# zx_kit3.net
KiCad netlist of a schematic drawn in EAGLE
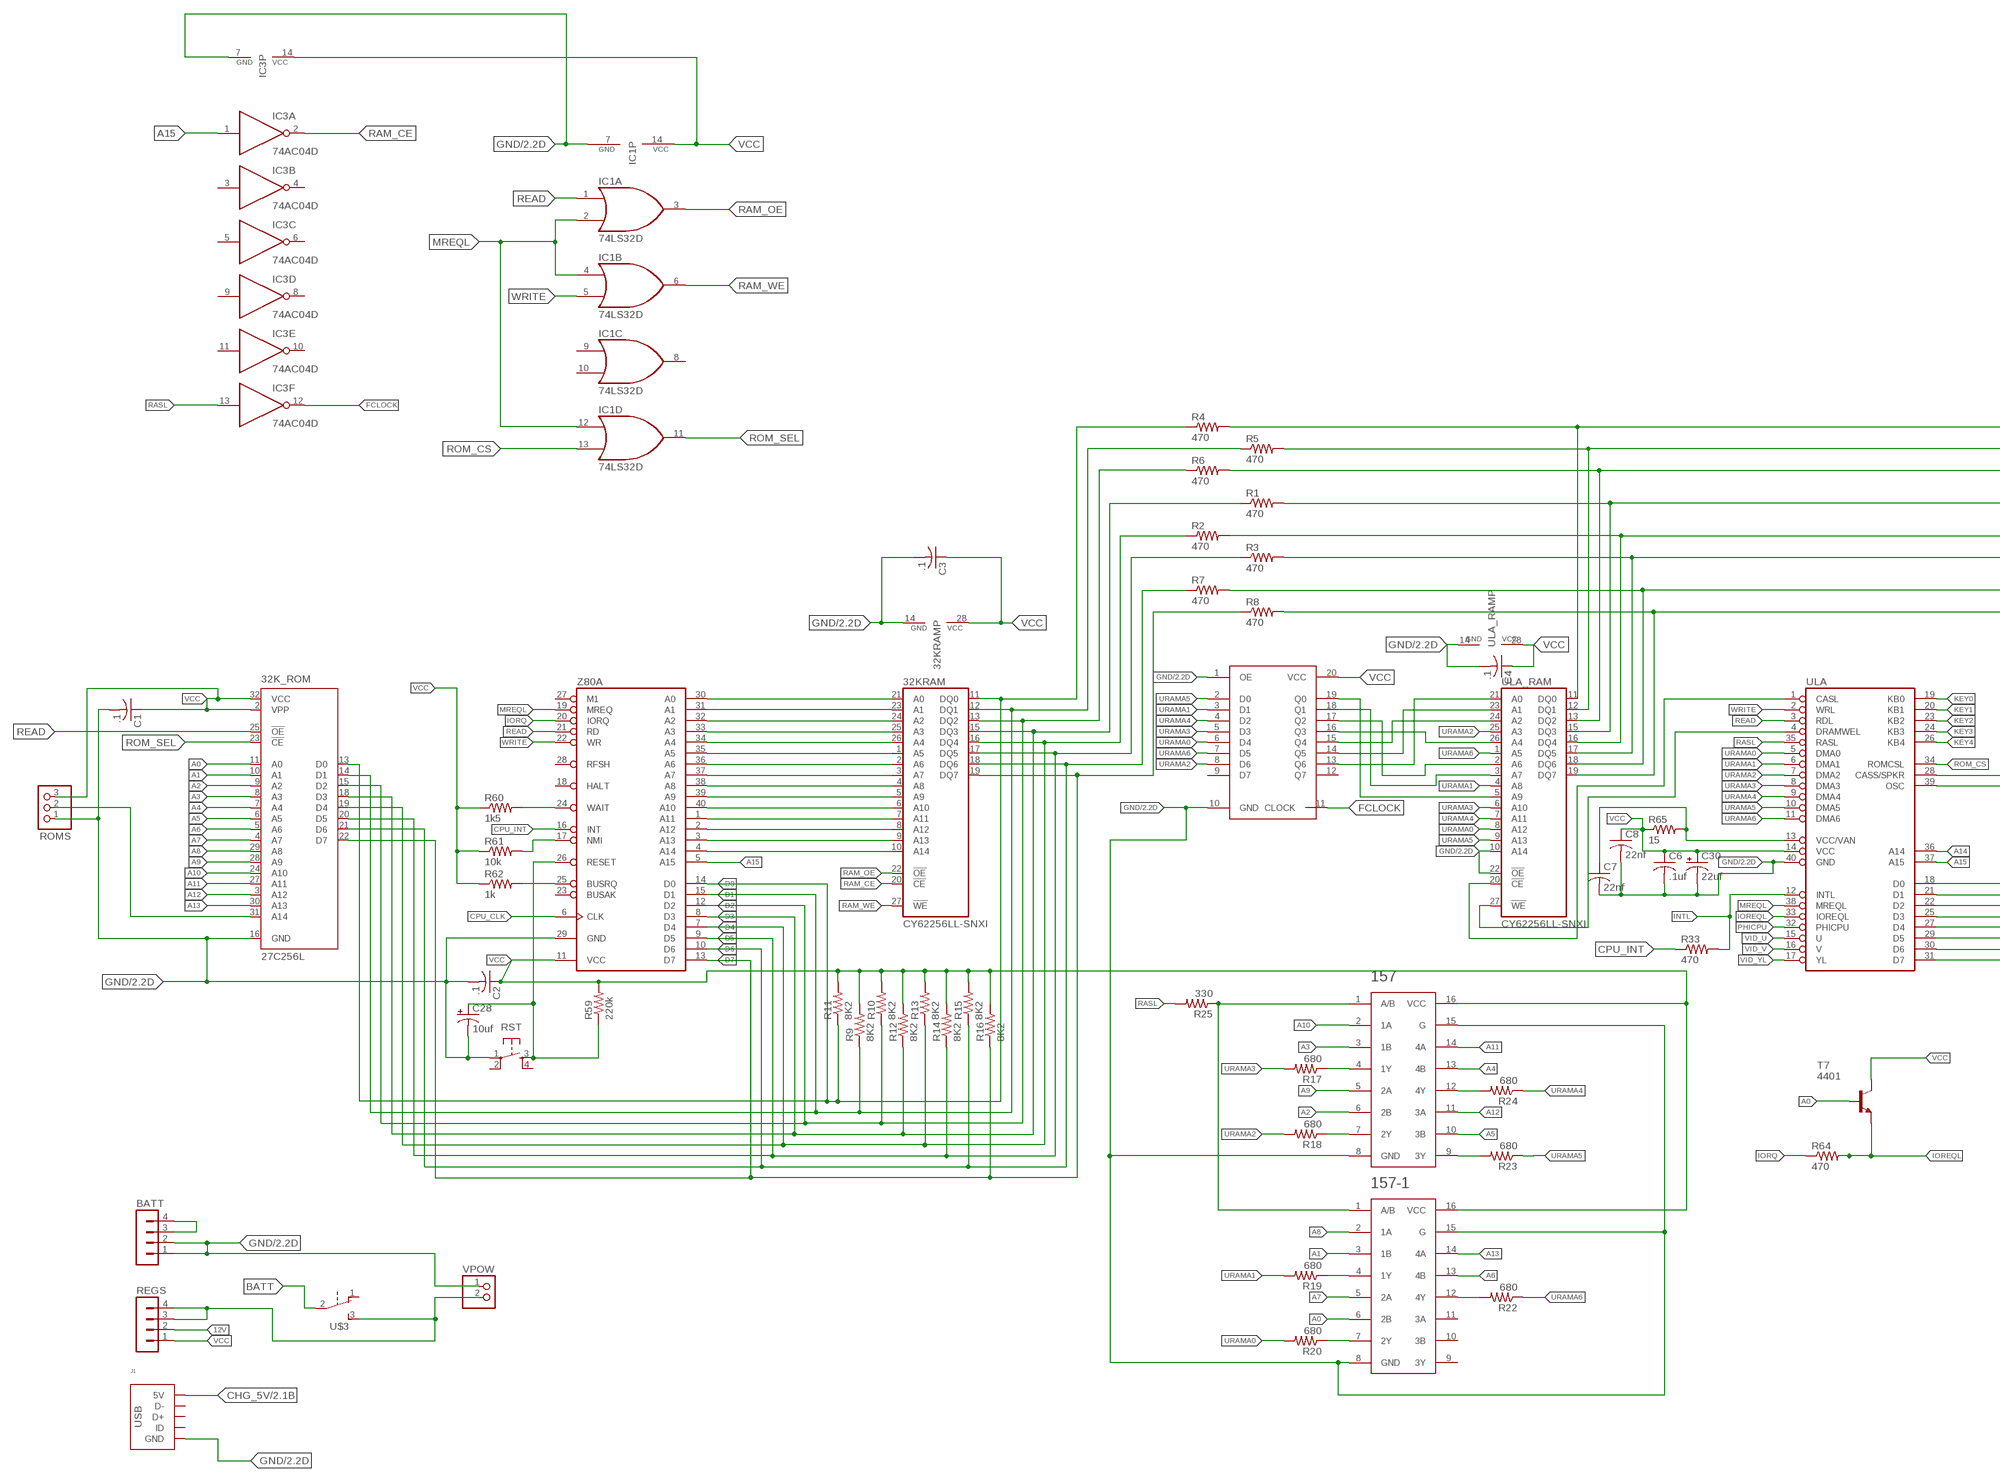
[diagram p0: schematic, sheet 1, part 1 of 3]
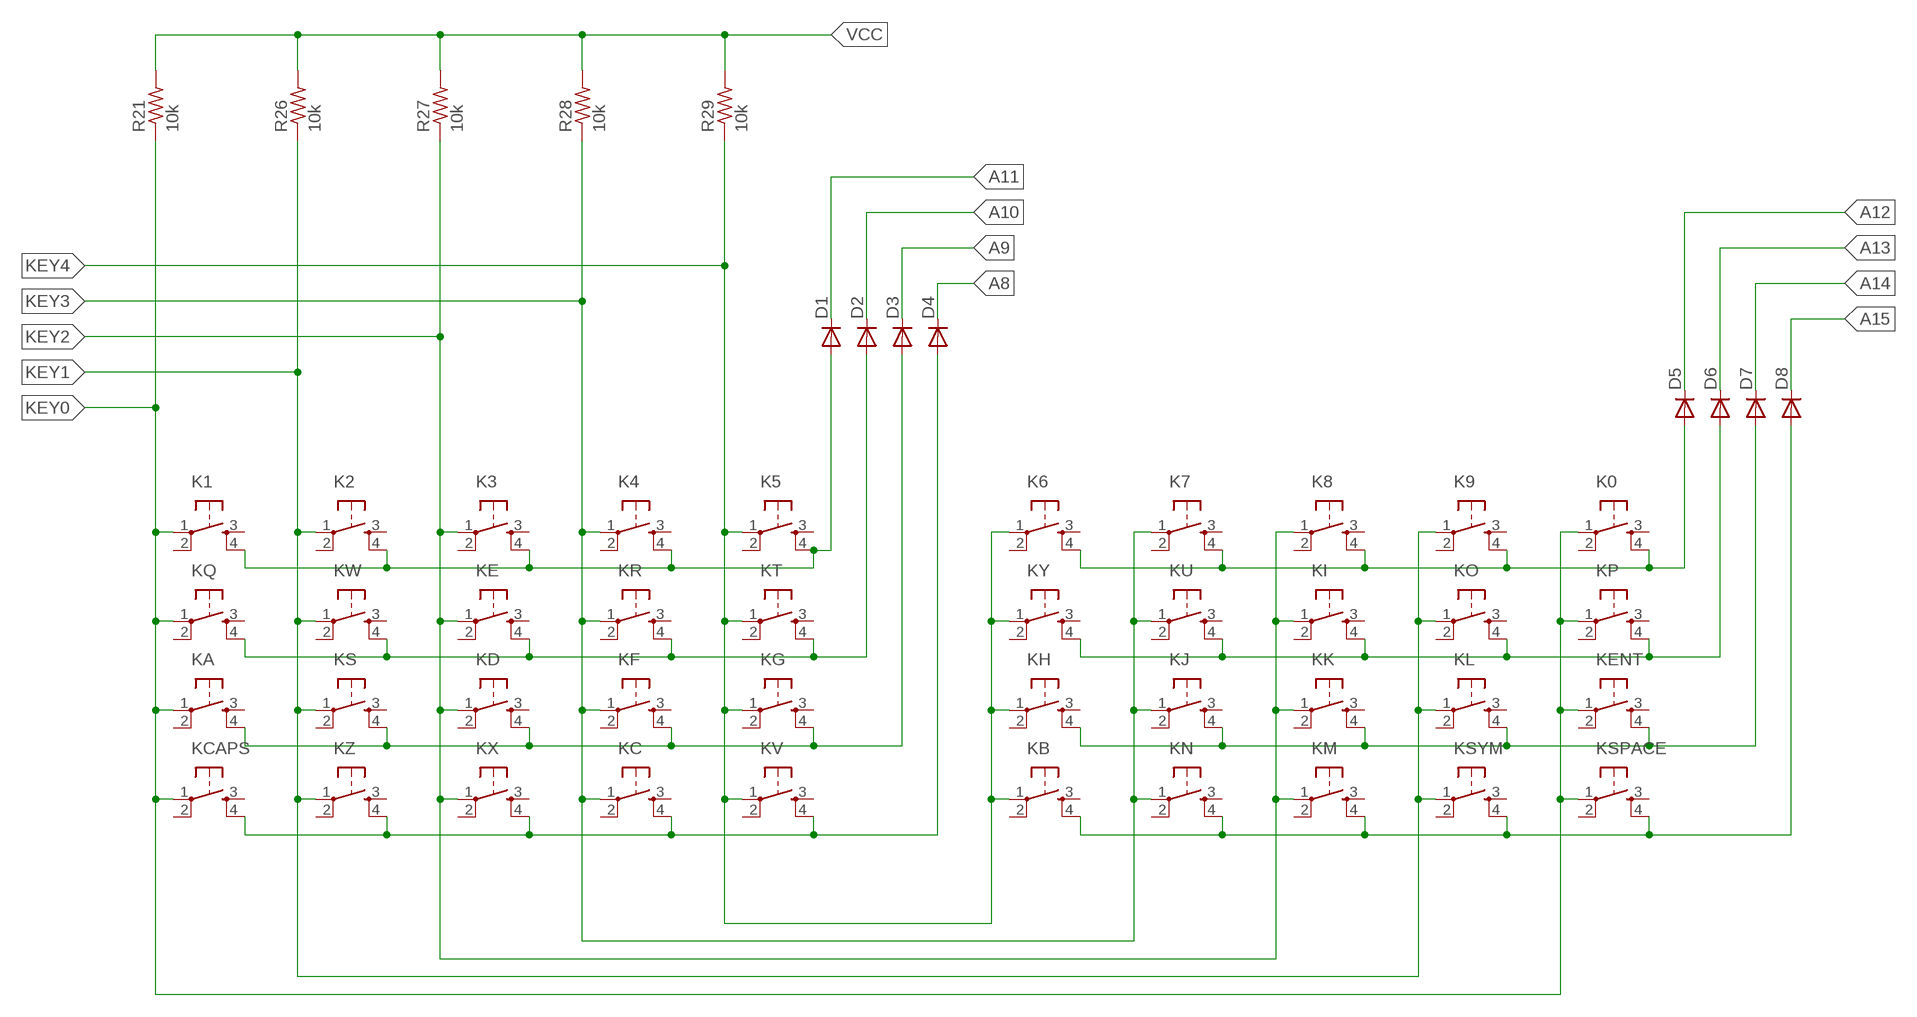
[diagram p1: schematic, sheet 1, part 2 of 3]
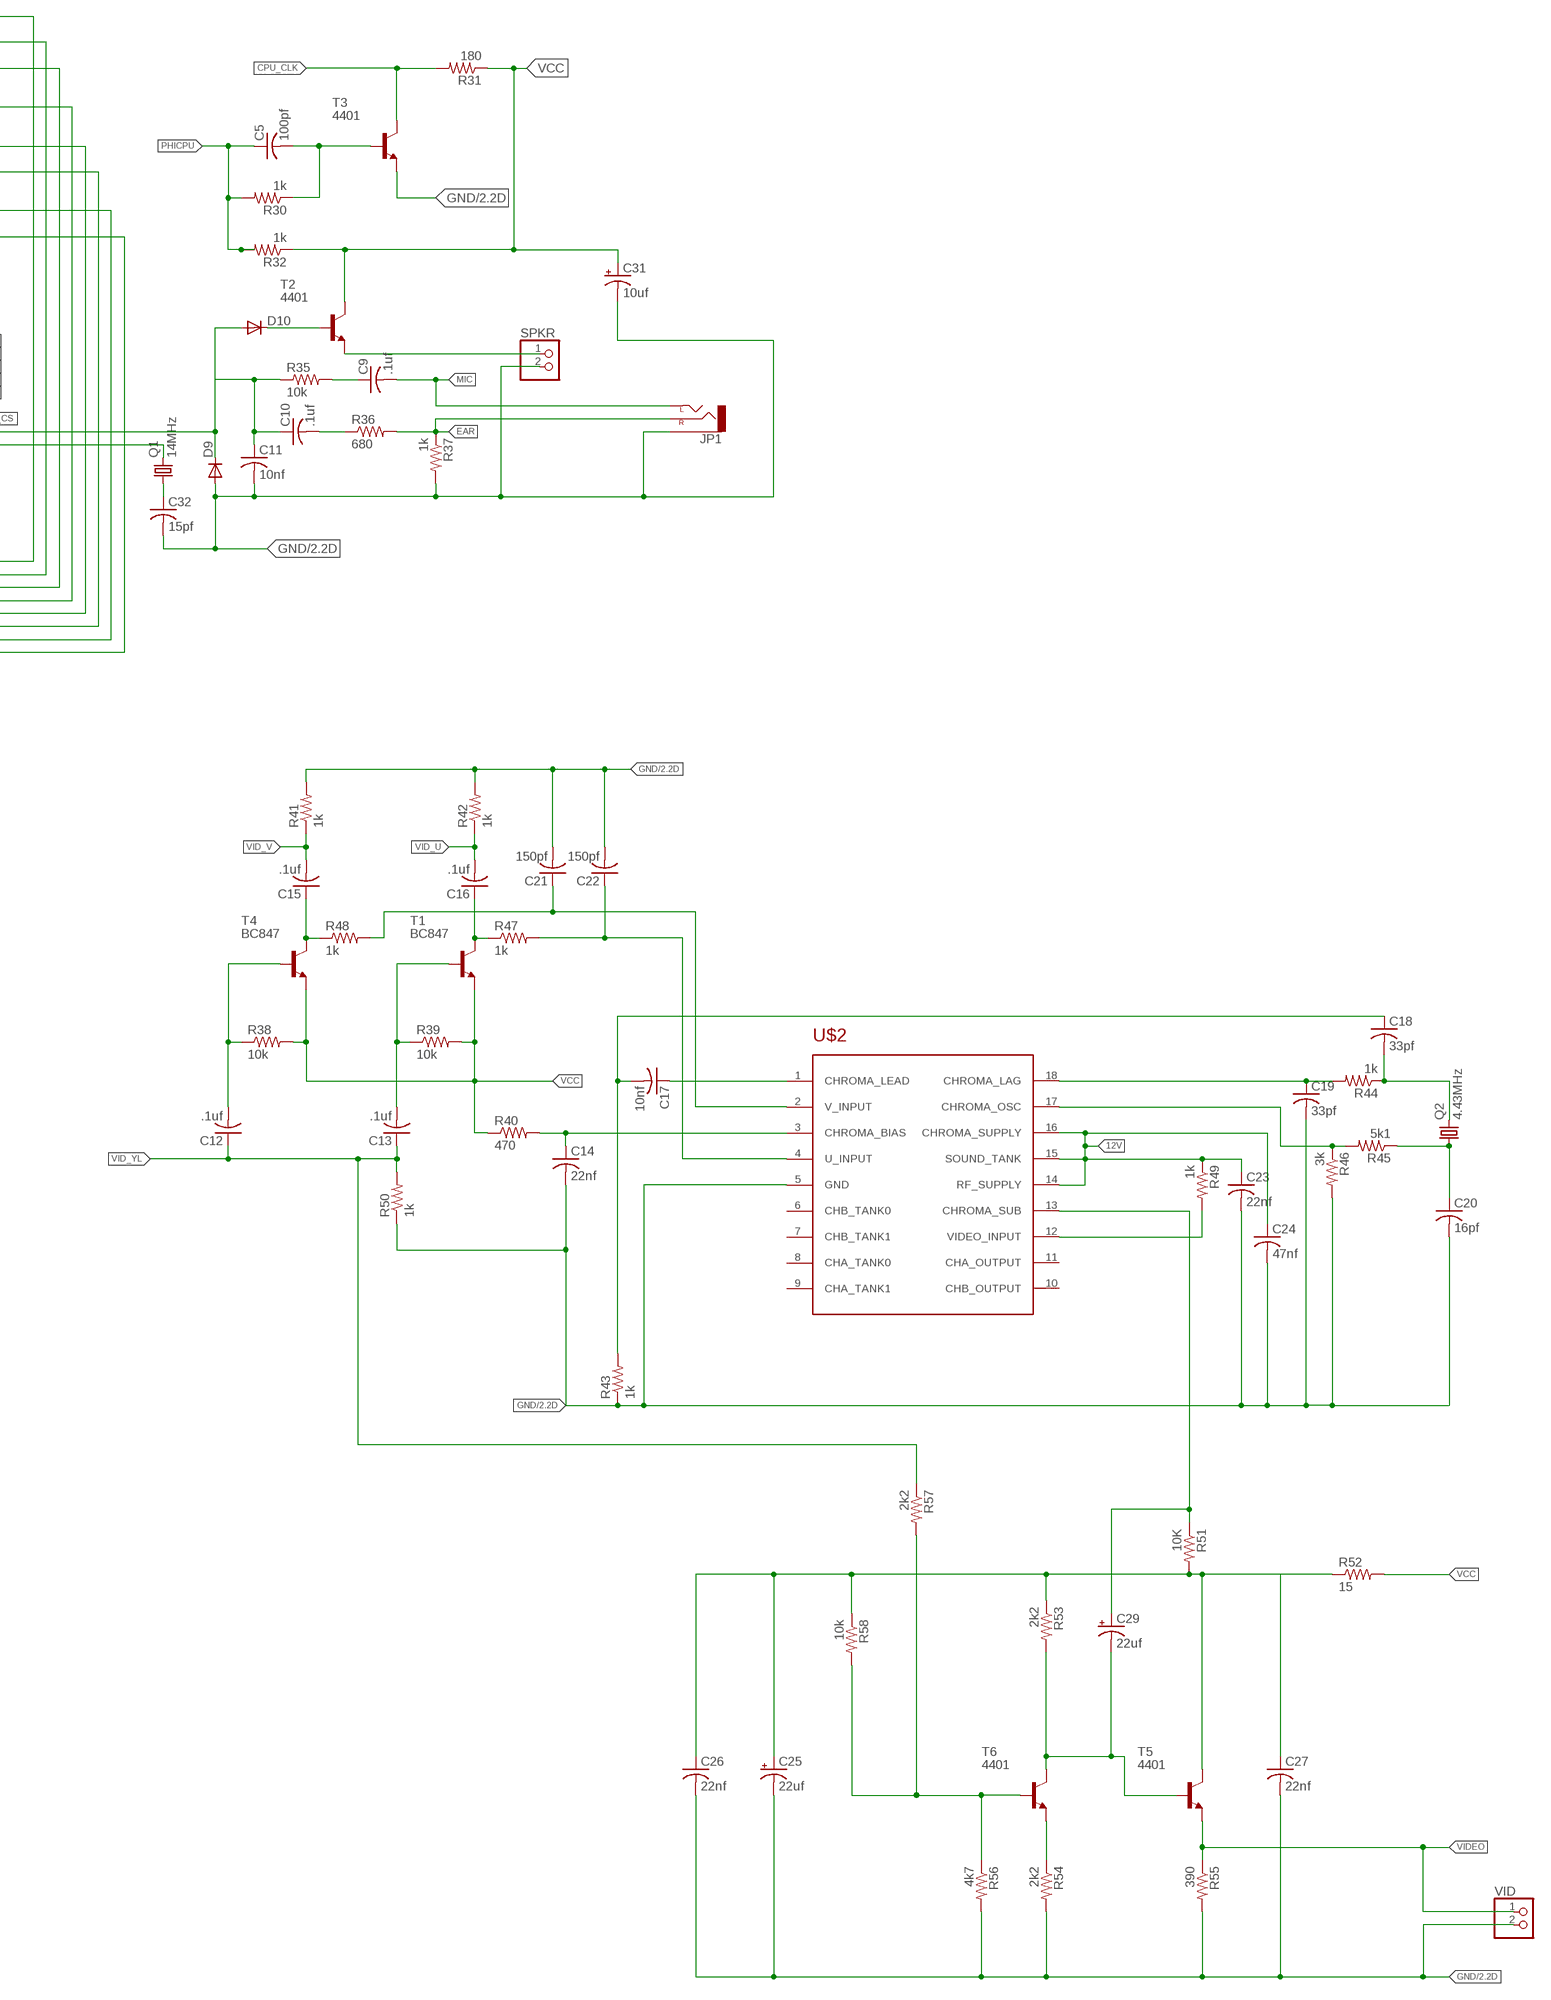
[diagram p2: schematic, sheet 1, part 3 of 3]
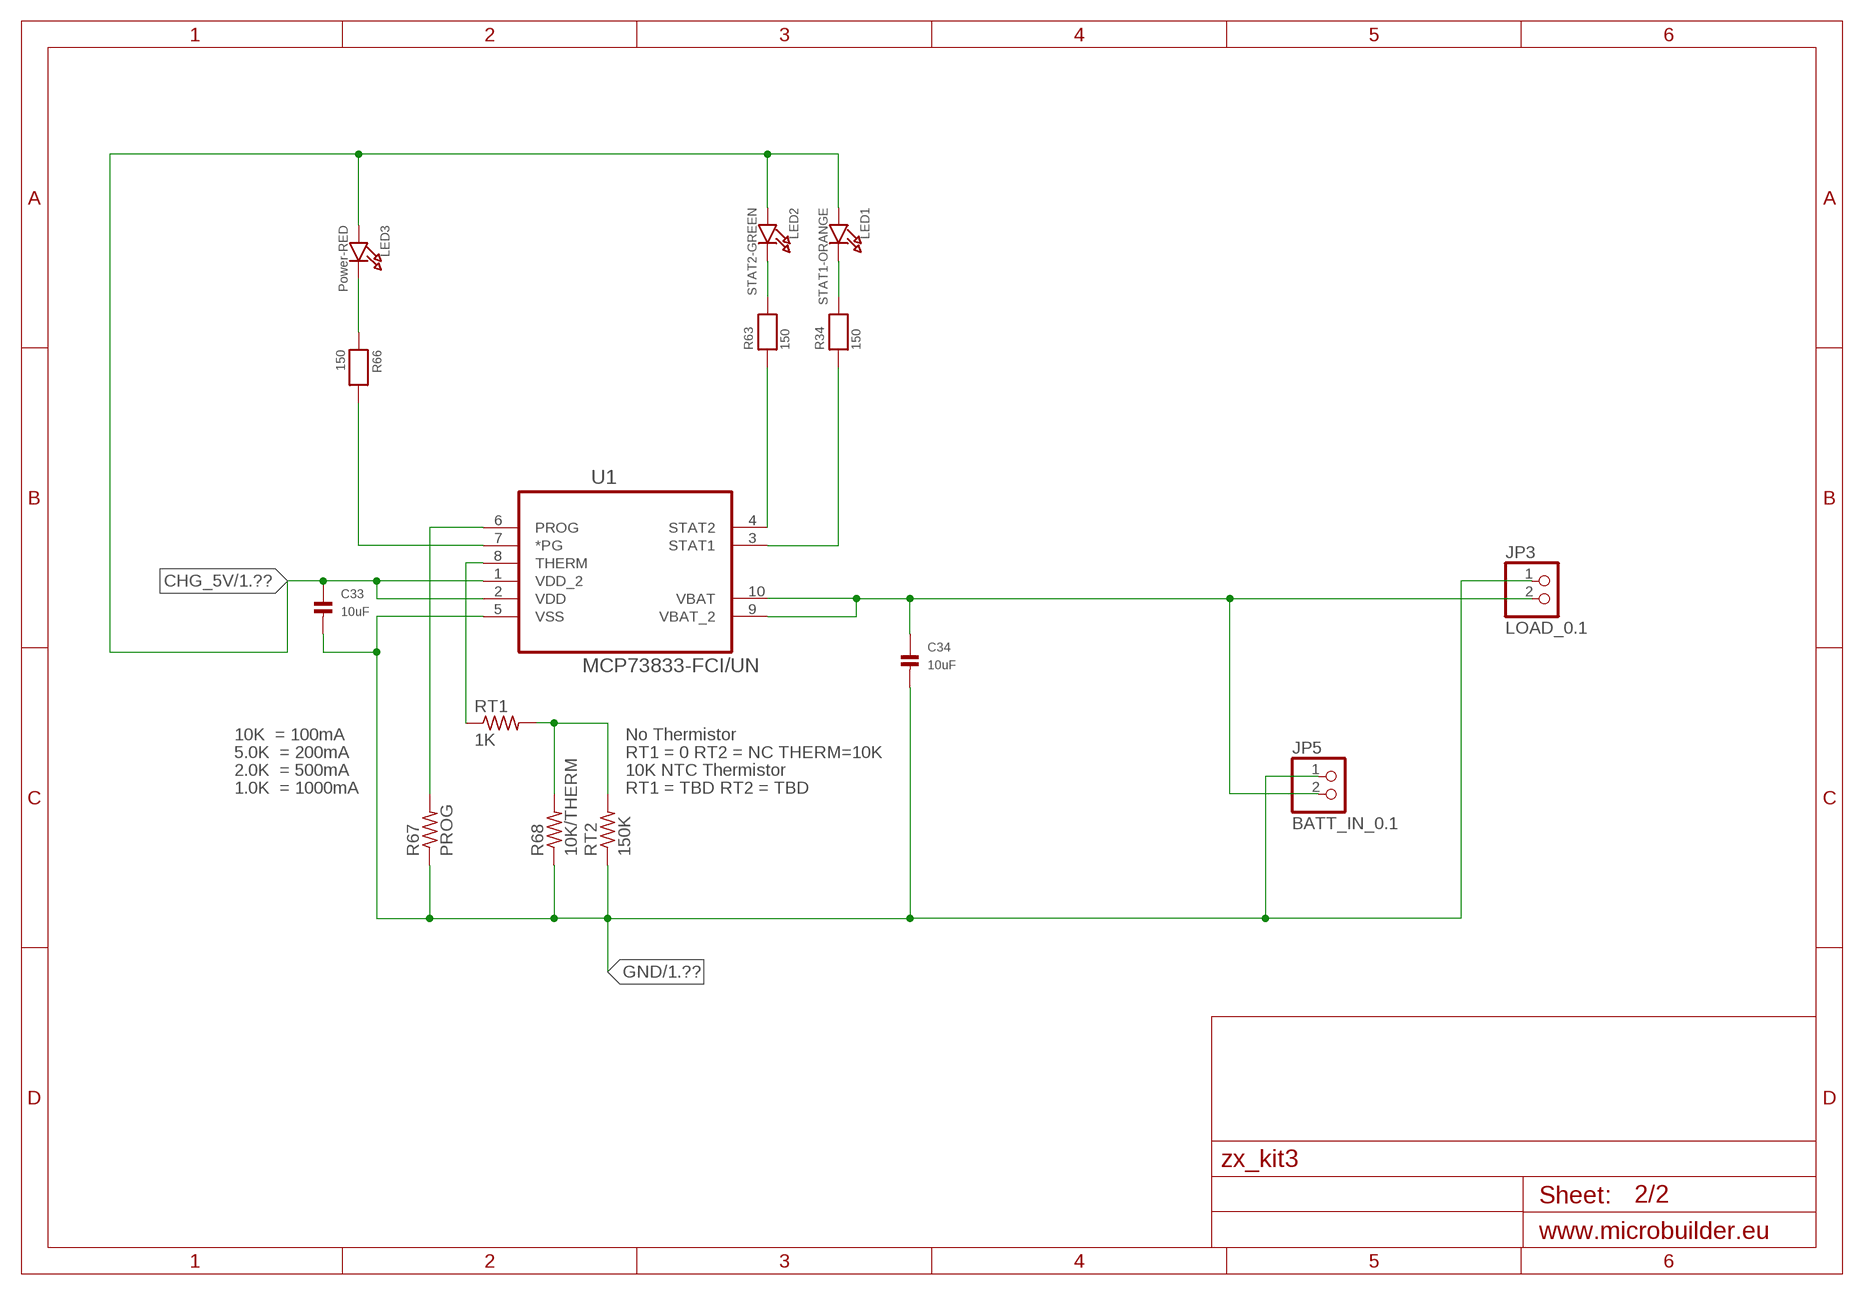
[diagram p3: schematic, sheet 2]

(export (version "E")
  (design (tool "Eeschema 10.0.6"))
  (components
    (comp (ref "32KRAM")
      (value "CY62256LL-SNXI")
      (footprint "eagle-import:SOJ28_3")
      (libsource (lib "eagle-import") (part "CY62256LL-?SNXI"))
    )
    (comp (ref "32K_ROM")
      (value "27C256L")
      (footprint "eagle-import:PLCC-32")
      (fields (field (name "MPN") "AT27C256R-70JU"))
      (libsource (lib "eagle-import") (part "27256LC"))
    )
    (comp (ref "157")
      (value "SN74HC157D")
      (footprint "eagle-import:SO16")
      (libsource (lib "eagle-import") (part "SN74HC157D"))
    )
    (comp (ref "157-1")
      (value "SN74HC157D")
      (footprint "eagle-import:SO16")
      (libsource (lib "eagle-import") (part "SN74HC157D"))
    )
    (comp (ref "BATT")
      (value "MA04-1")
      (footprint "eagle-import:MA04-1")
      (libsource (lib "eagle-import") (part "MA04-1"))
    )
    (comp (ref "C1")
      (value ".1")
      (footprint "eagle-import:C0805")
      (libsource (lib "eagle-import") (part "resistor_C-USC0805"))
    )
    (comp (ref "C2")
      (value ".1")
      (footprint "eagle-import:C0805")
      (libsource (lib "eagle-import") (part "resistor_C-USC0805"))
    )
    (comp (ref "C3")
      (value ".1")
      (footprint "eagle-import:C0805")
      (libsource (lib "eagle-import") (part "resistor_C-USC0805"))
    )
    (comp (ref "C4")
      (value ".1")
      (footprint "eagle-import:C0805")
      (libsource (lib "eagle-import") (part "resistor_C-USC0805"))
    )
    (comp (ref "C5")
      (value "100pf")
      (footprint "eagle-import:C0805")
      (libsource (lib "eagle-import") (part "C-USC0805"))
    )
    (comp (ref "C6")
      (value ".1uf")
      (footprint "eagle-import:C0805")
      (libsource (lib "eagle-import") (part "C-USC0805"))
    )
    (comp (ref "C7")
      (value "22nf")
      (footprint "eagle-import:C0805")
      (libsource (lib "eagle-import") (part "C-USC0805"))
    )
    (comp (ref "C8")
      (value "22nf")
      (footprint "eagle-import:C0805")
      (libsource (lib "eagle-import") (part "C-USC0805"))
    )
    (comp (ref "C9")
      (value ".1uf")
      (footprint "eagle-import:C0805")
      (libsource (lib "eagle-import") (part "C-USC0805"))
    )
    (comp (ref "C10")
      (value ".1uf")
      (footprint "eagle-import:C0805")
      (libsource (lib "eagle-import") (part "C-USC0805"))
    )
    (comp (ref "C11")
      (value "10nf")
      (footprint "eagle-import:C0805")
      (libsource (lib "eagle-import") (part "C-USC0805"))
    )
    (comp (ref "C12")
      (value ".1uf")
      (footprint "eagle-import:C0805")
      (libsource (lib "eagle-import") (part "C-USC0805"))
    )
    (comp (ref "C13")
      (value ".1uf")
      (footprint "eagle-import:C0805")
      (libsource (lib "eagle-import") (part "C-USC0805"))
    )
    (comp (ref "C14")
      (value "22nf")
      (footprint "eagle-import:C0805")
      (libsource (lib "eagle-import") (part "C-USC0805"))
    )
    (comp (ref "C15")
      (value ".1uf")
      (footprint "eagle-import:C0805")
      (libsource (lib "eagle-import") (part "C-USC0805"))
    )
    (comp (ref "C16")
      (value ".1uf")
      (footprint "eagle-import:C0805")
      (libsource (lib "eagle-import") (part "C-USC0805"))
    )
    (comp (ref "C17")
      (value "10nf")
      (footprint "eagle-import:C0805")
      (libsource (lib "eagle-import") (part "C-USC0805"))
    )
    (comp (ref "C18")
      (value "33pf")
      (footprint "eagle-import:C0805")
      (libsource (lib "eagle-import") (part "C-USC0805"))
    )
    (comp (ref "C19")
      (value "33pf")
      (footprint "eagle-import:C0805")
      (libsource (lib "eagle-import") (part "C-USC0805"))
    )
    (comp (ref "C20")
      (value "16pf")
      (footprint "eagle-import:C0805")
      (libsource (lib "eagle-import") (part "C-USC0805"))
    )
    (comp (ref "C21")
      (value "150pf")
      (footprint "eagle-import:C0805")
      (libsource (lib "eagle-import") (part "C-USC0805"))
    )
    (comp (ref "C22")
      (value "150pf")
      (footprint "eagle-import:C0805")
      (libsource (lib "eagle-import") (part "C-USC0805"))
    )
    (comp (ref "C23")
      (value "22nf")
      (footprint "eagle-import:C0805")
      (libsource (lib "eagle-import") (part "C-USC0805"))
    )
    (comp (ref "C24")
      (value "47nf")
      (footprint "eagle-import:C0805")
      (libsource (lib "eagle-import") (part "C-USC0805"))
    )
    (comp (ref "C25")
      (value "22uf")
      (footprint "eagle-import:PANASONIC_B")
      (libsource (lib "eagle-import") (part "CPOL-USB"))
    )
    (comp (ref "C26")
      (value "22nf")
      (footprint "eagle-import:C0805")
      (libsource (lib "eagle-import") (part "C-USC0805"))
    )
    (comp (ref "C27")
      (value "22nf")
      (footprint "eagle-import:C0805")
      (libsource (lib "eagle-import") (part "C-USC0805"))
    )
    (comp (ref "C28")
      (value "10uf")
      (footprint "eagle-import:PANASONIC_B")
      (libsource (lib "eagle-import") (part "CPOL-USB"))
    )
    (comp (ref "C29")
      (value "22uf")
      (footprint "eagle-import:PANASONIC_B")
      (libsource (lib "eagle-import") (part "CPOL-USB"))
    )
    (comp (ref "C30")
      (value "22uf")
      (footprint "eagle-import:PANASONIC_B")
      (libsource (lib "eagle-import") (part "CPOL-USB"))
    )
    (comp (ref "C31")
      (value "10uf")
      (footprint "eagle-import:PANASONIC_B")
      (libsource (lib "eagle-import") (part "CPOL-USB"))
    )
    (comp (ref "C32")
      (value "15pf")
      (footprint "eagle-import:C0805")
      (libsource (lib "eagle-import") (part "C-USC0805"))
    )
    (comp (ref "D1")
      (value "DIODE-SOD123")
      (footprint "eagle-import:SOD123")
      (libsource (lib "eagle-import") (part "DIODE-SOD123"))
    )
    (comp (ref "D2")
      (value "DIODE-SOD123")
      (footprint "eagle-import:SOD123")
      (libsource (lib "eagle-import") (part "DIODE-SOD123"))
    )
    (comp (ref "D3")
      (value "DIODE-SOD123")
      (footprint "eagle-import:SOD123")
      (libsource (lib "eagle-import") (part "DIODE-SOD123"))
    )
    (comp (ref "D4")
      (value "DIODE-SOD123")
      (footprint "eagle-import:SOD123")
      (libsource (lib "eagle-import") (part "DIODE-SOD123"))
    )
    (comp (ref "D5")
      (value "DIODE-SOD123")
      (footprint "eagle-import:SOD123")
      (libsource (lib "eagle-import") (part "DIODE-SOD123"))
    )
    (comp (ref "D6")
      (value "DIODE-SOD123")
      (footprint "eagle-import:SOD123")
      (libsource (lib "eagle-import") (part "DIODE-SOD123"))
    )
    (comp (ref "D7")
      (value "DIODE-SOD123")
      (footprint "eagle-import:SOD123")
      (libsource (lib "eagle-import") (part "DIODE-SOD123"))
    )
    (comp (ref "D8")
      (value "DIODE-SOD123")
      (footprint "eagle-import:SOD123")
      (libsource (lib "eagle-import") (part "DIODE-SOD123"))
    )
    (comp (ref "D9")
      (value "DIODE-SOD123")
      (footprint "eagle-import:SOD123")
      (libsource (lib "eagle-import") (part "DIODE-SOD123"))
    )
    (comp (ref "D10")
      (value "DIODE-SOD123")
      (footprint "eagle-import:SOD123")
      (libsource (lib "eagle-import") (part "DIODE-SOD123"))
    )
    (comp (ref "IC1")
      (value "74LS32D")
      (footprint "eagle-import:SO14")
      (libsource (lib "eagle-import") (part "7432DLS"))
    )
    (comp (ref "IC3")
      (value "74AC04D")
      (footprint "eagle-import:SO14")
      (libsource (lib "eagle-import") (part "7404DAC"))
    )
    (comp (ref "J1")
      (value "USBMC32599")
      (footprint "eagle-import:MC32599")
      (libsource (lib "eagle-import") (part "USBMC32599"))
    )
    (comp (ref "JP1")
      (value "AUDIO-JACKPTH")
      (footprint "eagle-import:AUDIO-JACK")
      (libsource (lib "eagle-import") (part "AUDIO-JACKPTH"))
    )
    (comp (ref "K0")
      (value "DTS-6")
      (footprint "eagle-import:DTS-6")
      (libsource (lib "eagle-import") (part "DTS-6"))
    )
    (comp (ref "K1")
      (value "DTS-6")
      (footprint "eagle-import:DTS-6")
      (libsource (lib "eagle-import") (part "DTS-6"))
    )
    (comp (ref "K2")
      (value "DTS-6")
      (footprint "eagle-import:DTS-6")
      (libsource (lib "eagle-import") (part "DTS-6"))
    )
    (comp (ref "K3")
      (value "DTS-6")
      (footprint "eagle-import:DTS-6")
      (libsource (lib "eagle-import") (part "DTS-6"))
    )
    (comp (ref "K4")
      (value "DTS-6")
      (footprint "eagle-import:DTS-6")
      (libsource (lib "eagle-import") (part "DTS-6"))
    )
    (comp (ref "K5")
      (value "DTS-6")
      (footprint "eagle-import:DTS-6")
      (libsource (lib "eagle-import") (part "DTS-6"))
    )
    (comp (ref "K6")
      (value "DTS-6")
      (footprint "eagle-import:DTS-6")
      (libsource (lib "eagle-import") (part "DTS-6"))
    )
    (comp (ref "K7")
      (value "DTS-6")
      (footprint "eagle-import:DTS-6")
      (libsource (lib "eagle-import") (part "DTS-6"))
    )
    (comp (ref "K8")
      (value "DTS-6")
      (footprint "eagle-import:DTS-6")
      (libsource (lib "eagle-import") (part "DTS-6"))
    )
    (comp (ref "K9")
      (value "DTS-6")
      (footprint "eagle-import:DTS-6")
      (libsource (lib "eagle-import") (part "DTS-6"))
    )
    (comp (ref "KA")
      (value "DTS-6")
      (footprint "eagle-import:DTS-6")
      (libsource (lib "eagle-import") (part "DTS-6"))
    )
    (comp (ref "KB")
      (value "DTS-6")
      (footprint "eagle-import:DTS-6")
      (libsource (lib "eagle-import") (part "DTS-6"))
    )
    (comp (ref "KC")
      (value "DTS-6")
      (footprint "eagle-import:DTS-6")
      (libsource (lib "eagle-import") (part "DTS-6"))
    )
    (comp (ref "KCAPS")
      (value "DTS-6")
      (footprint "eagle-import:DTS-6")
      (libsource (lib "eagle-import") (part "DTS-6"))
    )
    (comp (ref "KD")
      (value "DTS-6")
      (footprint "eagle-import:DTS-6")
      (libsource (lib "eagle-import") (part "DTS-6"))
    )
    (comp (ref "KE")
      (value "DTS-6")
      (footprint "eagle-import:DTS-6")
      (libsource (lib "eagle-import") (part "DTS-6"))
    )
    (comp (ref "KENT")
      (value "DTS-6")
      (footprint "eagle-import:DTS-6")
      (libsource (lib "eagle-import") (part "DTS-6"))
    )
    (comp (ref "KF")
      (value "DTS-6")
      (footprint "eagle-import:DTS-6")
      (libsource (lib "eagle-import") (part "DTS-6"))
    )
    (comp (ref "KG")
      (value "DTS-6")
      (footprint "eagle-import:DTS-6")
      (libsource (lib "eagle-import") (part "DTS-6"))
    )
    (comp (ref "KH")
      (value "DTS-6")
      (footprint "eagle-import:DTS-6")
      (libsource (lib "eagle-import") (part "DTS-6"))
    )
    (comp (ref "KI")
      (value "DTS-6")
      (footprint "eagle-import:DTS-6")
      (libsource (lib "eagle-import") (part "DTS-6"))
    )
    (comp (ref "KJ")
      (value "DTS-6")
      (footprint "eagle-import:DTS-6")
      (libsource (lib "eagle-import") (part "DTS-6"))
    )
    (comp (ref "KK")
      (value "DTS-6")
      (footprint "eagle-import:DTS-6")
      (libsource (lib "eagle-import") (part "DTS-6"))
    )
    (comp (ref "KL")
      (value "DTS-6")
      (footprint "eagle-import:DTS-6")
      (libsource (lib "eagle-import") (part "DTS-6"))
    )
    (comp (ref "KM")
      (value "DTS-6")
      (footprint "eagle-import:DTS-6")
      (libsource (lib "eagle-import") (part "DTS-6"))
    )
    (comp (ref "KN")
      (value "DTS-6")
      (footprint "eagle-import:DTS-6")
      (libsource (lib "eagle-import") (part "DTS-6"))
    )
    (comp (ref "KO")
      (value "DTS-6")
      (footprint "eagle-import:DTS-6")
      (libsource (lib "eagle-import") (part "DTS-6"))
    )
    (comp (ref "KP")
      (value "DTS-6")
      (footprint "eagle-import:DTS-6")
      (libsource (lib "eagle-import") (part "DTS-6"))
    )
    (comp (ref "KQ")
      (value "DTS-6")
      (footprint "eagle-import:DTS-6")
      (libsource (lib "eagle-import") (part "DTS-6"))
    )
    (comp (ref "KR")
      (value "DTS-6")
      (footprint "eagle-import:DTS-6")
      (libsource (lib "eagle-import") (part "DTS-6"))
    )
    (comp (ref "KS")
      (value "DTS-6")
      (footprint "eagle-import:DTS-6")
      (libsource (lib "eagle-import") (part "DTS-6"))
    )
    (comp (ref "KSPACE")
      (value "DTS-6")
      (footprint "eagle-import:DTS-6")
      (libsource (lib "eagle-import") (part "DTS-6"))
    )
    (comp (ref "KSYM")
      (value "DTS-6")
      (footprint "eagle-import:DTS-6")
      (libsource (lib "eagle-import") (part "DTS-6"))
    )
    (comp (ref "KT")
      (value "DTS-6")
      (footprint "eagle-import:DTS-6")
      (libsource (lib "eagle-import") (part "DTS-6"))
    )
    (comp (ref "KU")
      (value "DTS-6")
      (footprint "eagle-import:DTS-6")
      (libsource (lib "eagle-import") (part "DTS-6"))
    )
    (comp (ref "KV")
      (value "DTS-6")
      (footprint "eagle-import:DTS-6")
      (libsource (lib "eagle-import") (part "DTS-6"))
    )
    (comp (ref "KW")
      (value "DTS-6")
      (footprint "eagle-import:DTS-6")
      (libsource (lib "eagle-import") (part "DTS-6"))
    )
    (comp (ref "KX")
      (value "DTS-6")
      (footprint "eagle-import:DTS-6")
      (libsource (lib "eagle-import") (part "DTS-6"))
    )
    (comp (ref "KY")
      (value "DTS-6")
      (footprint "eagle-import:DTS-6")
      (libsource (lib "eagle-import") (part "DTS-6"))
    )
    (comp (ref "KZ")
      (value "DTS-6")
      (footprint "eagle-import:DTS-6")
      (libsource (lib "eagle-import") (part "DTS-6"))
    )
    (comp (ref "Q1")
      (value "14MHz")
      (footprint "eagle-import:CTS406")
      (libsource (lib "eagle-import") (part "CRYSTALCTS406"))
    )
    (comp (ref "Q2")
      (value "4.43MHz")
      (footprint "eagle-import:HC49_S")
      (libsource (lib "eagle-import") (part "CRYSTALHC49S"))
    )
    (comp (ref "R1")
      (value "470")
      (footprint "eagle-import:M0805")
      (libsource (lib "eagle-import") (part "resistor_R-US_M0805"))
    )
    (comp (ref "R2")
      (value "470")
      (footprint "eagle-import:M0805")
      (libsource (lib "eagle-import") (part "resistor_R-US_M0805"))
    )
    (comp (ref "R3")
      (value "470")
      (footprint "eagle-import:M0805")
      (libsource (lib "eagle-import") (part "resistor_R-US_M0805"))
    )
    (comp (ref "R4")
      (value "470")
      (footprint "eagle-import:M0805")
      (libsource (lib "eagle-import") (part "resistor_R-US_M0805"))
    )
    (comp (ref "R5")
      (value "470")
      (footprint "eagle-import:M0805")
      (libsource (lib "eagle-import") (part "resistor_R-US_M0805"))
    )
    (comp (ref "R6")
      (value "470")
      (footprint "eagle-import:M0805")
      (libsource (lib "eagle-import") (part "resistor_R-US_M0805"))
    )
    (comp (ref "R7")
      (value "470")
      (footprint "eagle-import:M0805")
      (libsource (lib "eagle-import") (part "resistor_R-US_M0805"))
    )
    (comp (ref "R8")
      (value "470")
      (footprint "eagle-import:M0805")
      (libsource (lib "eagle-import") (part "resistor_R-US_M0805"))
    )
    (comp (ref "R9")
      (value "8K2")
      (footprint "eagle-import:M0805")
      (libsource (lib "eagle-import") (part "resistor_R-US_M0805"))
    )
    (comp (ref "R10")
      (value "8K2")
      (footprint "eagle-import:M0805")
      (libsource (lib "eagle-import") (part "resistor_R-US_M0805"))
    )
    (comp (ref "R11")
      (value "8K2")
      (footprint "eagle-import:M0805")
      (libsource (lib "eagle-import") (part "resistor_R-US_M0805"))
    )
    (comp (ref "R12")
      (value "8K2")
      (footprint "eagle-import:M0805")
      (libsource (lib "eagle-import") (part "resistor_R-US_M0805"))
    )
    (comp (ref "R13")
      (value "8K2")
      (footprint "eagle-import:M0805")
      (libsource (lib "eagle-import") (part "resistor_R-US_M0805"))
    )
    (comp (ref "R14")
      (value "8K2")
      (footprint "eagle-import:M0805")
      (libsource (lib "eagle-import") (part "resistor_R-US_M0805"))
    )
    (comp (ref "R15")
      (value "8K2")
      (footprint "eagle-import:M0805")
      (libsource (lib "eagle-import") (part "resistor_R-US_M0805"))
    )
    (comp (ref "R16")
      (value "8K2")
      (footprint "eagle-import:M0805")
      (libsource (lib "eagle-import") (part "resistor_R-US_M0805"))
    )
    (comp (ref "R17")
      (value "680")
      (footprint "eagle-import:M0805")
      (libsource (lib "eagle-import") (part "resistor_R-US_M0805"))
    )
    (comp (ref "R18")
      (value "680")
      (footprint "eagle-import:M0805")
      (libsource (lib "eagle-import") (part "resistor_R-US_M0805"))
    )
    (comp (ref "R19")
      (value "680")
      (footprint "eagle-import:M0805")
      (libsource (lib "eagle-import") (part "resistor_R-US_M0805"))
    )
    (comp (ref "R20")
      (value "680")
      (footprint "eagle-import:M0805")
      (libsource (lib "eagle-import") (part "resistor_R-US_M0805"))
    )
    (comp (ref "R21")
      (value "10k")
      (footprint "eagle-import:R0805")
      (libsource (lib "eagle-import") (part "resistor_R-US_R0805"))
    )
    (comp (ref "R22")
      (value "680")
      (footprint "eagle-import:M0805")
      (libsource (lib "eagle-import") (part "resistor_R-US_M0805"))
    )
    (comp (ref "R23")
      (value "680")
      (footprint "eagle-import:M0805")
      (libsource (lib "eagle-import") (part "resistor_R-US_M0805"))
    )
    (comp (ref "R24")
      (value "680")
      (footprint "eagle-import:M0805")
      (libsource (lib "eagle-import") (part "resistor_R-US_M0805"))
    )
    (comp (ref "R25")
      (value "330")
      (footprint "eagle-import:M0805")
      (libsource (lib "eagle-import") (part "resistor_R-US_M0805"))
    )
    (comp (ref "R26")
      (value "10k")
      (footprint "eagle-import:R0805")
      (libsource (lib "eagle-import") (part "resistor_R-US_R0805"))
    )
    (comp (ref "R27")
      (value "10k")
      (footprint "eagle-import:R0805")
      (libsource (lib "eagle-import") (part "resistor_R-US_R0805"))
    )
    (comp (ref "R28")
      (value "10k")
      (footprint "eagle-import:R0805")
      (libsource (lib "eagle-import") (part "resistor_R-US_R0805"))
    )
    (comp (ref "R29")
      (value "10k")
      (footprint "eagle-import:R0805")
      (libsource (lib "eagle-import") (part "resistor_R-US_R0805"))
    )
    (comp (ref "R30")
      (value "1k")
      (footprint "eagle-import:R0805")
      (libsource (lib "eagle-import") (part "resistor_R-US_R0805"))
    )
    (comp (ref "R31")
      (value "180")
      (footprint "eagle-import:R0805")
      (libsource (lib "eagle-import") (part "resistor_R-US_R0805"))
    )
    (comp (ref "R32")
      (value "1k")
      (footprint "eagle-import:R0805")
      (libsource (lib "eagle-import") (part "resistor_R-US_R0805"))
    )
    (comp (ref "R33")
      (value "470")
      (footprint "eagle-import:R0805")
      (libsource (lib "eagle-import") (part "resistor_R-US_R0805"))
    )
    (comp (ref "R35")
      (value "10k")
      (footprint "eagle-import:R0805")
      (libsource (lib "eagle-import") (part "resistor_R-US_R0805"))
    )
    (comp (ref "R36")
      (value "680")
      (footprint "eagle-import:R0805")
      (libsource (lib "eagle-import") (part "resistor_R-US_R0805"))
    )
    (comp (ref "R37")
      (value "1k")
      (footprint "eagle-import:R0805")
      (libsource (lib "eagle-import") (part "resistor_R-US_R0805"))
    )
    (comp (ref "R38")
      (value "10k")
      (footprint "eagle-import:R0805")
      (libsource (lib "eagle-import") (part "resistor_R-US_R0805"))
    )
    (comp (ref "R39")
      (value "10k")
      (footprint "eagle-import:R0805")
      (libsource (lib "eagle-import") (part "resistor_R-US_R0805"))
    )
    (comp (ref "R40")
      (value "470")
      (footprint "eagle-import:R0805")
      (libsource (lib "eagle-import") (part "resistor_R-US_R0805"))
    )
    (comp (ref "R41")
      (value "1k")
      (footprint "eagle-import:R0805")
      (libsource (lib "eagle-import") (part "resistor_R-US_R0805"))
    )
    (comp (ref "R42")
      (value "1k")
      (footprint "eagle-import:R0805")
      (libsource (lib "eagle-import") (part "resistor_R-US_R0805"))
    )
    (comp (ref "R43")
      (value "1k")
      (footprint "eagle-import:R0805")
      (libsource (lib "eagle-import") (part "resistor_R-US_R0805"))
    )
    (comp (ref "R44")
      (value "1k")
      (footprint "eagle-import:R0805")
      (libsource (lib "eagle-import") (part "resistor_R-US_R0805"))
    )
    (comp (ref "R45")
      (value "5k1")
      (footprint "eagle-import:R0805")
      (libsource (lib "eagle-import") (part "resistor_R-US_R0805"))
    )
    (comp (ref "R46")
      (value "3k")
      (footprint "eagle-import:R0805")
      (libsource (lib "eagle-import") (part "resistor_R-US_R0805"))
    )
    (comp (ref "R47")
      (value "1k")
      (footprint "eagle-import:R0805")
      (libsource (lib "eagle-import") (part "resistor_R-US_R0805"))
    )
    (comp (ref "R48")
      (value "1k")
      (footprint "eagle-import:R0805")
      (libsource (lib "eagle-import") (part "resistor_R-US_R0805"))
    )
    (comp (ref "R49")
      (value "1k")
      (footprint "eagle-import:R0805")
      (libsource (lib "eagle-import") (part "resistor_R-US_R0805"))
    )
    (comp (ref "R50")
      (value "1k")
      (footprint "eagle-import:R0805")
      (libsource (lib "eagle-import") (part "resistor_R-US_R0805"))
    )
    (comp (ref "R51")
      (value "10K")
      (footprint "eagle-import:R0805")
      (libsource (lib "eagle-import") (part "resistor_R-US_R0805"))
    )
    (comp (ref "R52")
      (value "15")
      (footprint "eagle-import:R0805")
      (libsource (lib "eagle-import") (part "resistor_R-US_R0805"))
    )
    (comp (ref "R53")
      (value "2k2")
      (footprint "eagle-import:R0805")
      (libsource (lib "eagle-import") (part "resistor_R-US_R0805"))
    )
    (comp (ref "R54")
      (value "2k2")
      (footprint "eagle-import:R0805")
      (libsource (lib "eagle-import") (part "resistor_R-US_R0805"))
    )
    (comp (ref "R55")
      (value "390")
      (footprint "eagle-import:R0805")
      (libsource (lib "eagle-import") (part "resistor_R-US_R0805"))
    )
    (comp (ref "R56")
      (value "4k7")
      (footprint "eagle-import:R0805")
      (libsource (lib "eagle-import") (part "resistor_R-US_R0805"))
    )
    (comp (ref "R57")
      (value "2k2")
      (footprint "eagle-import:R0805")
      (libsource (lib "eagle-import") (part "resistor_R-US_R0805"))
    )
    (comp (ref "R58")
      (value "10k")
      (footprint "eagle-import:R0805")
      (libsource (lib "eagle-import") (part "resistor_R-US_R0805"))
    )
    (comp (ref "R59")
      (value "220k")
      (footprint "eagle-import:M0805")
      (libsource (lib "eagle-import") (part "resistor_R-US_M0805"))
    )
    (comp (ref "R60")
      (value "1k5")
      (footprint "eagle-import:M0805")
      (libsource (lib "eagle-import") (part "resistor_R-US_M0805"))
    )
    (comp (ref "R61")
      (value "10k")
      (footprint "eagle-import:M0805")
      (libsource (lib "eagle-import") (part "resistor_R-US_M0805"))
    )
    (comp (ref "R62")
      (value "1k")
      (footprint "eagle-import:M0805")
      (libsource (lib "eagle-import") (part "resistor_R-US_M0805"))
    )
    (comp (ref "R64")
      (value "470")
      (footprint "eagle-import:R0805")
      (libsource (lib "eagle-import") (part "resistor_R-US_R0805"))
    )
    (comp (ref "R65")
      (value "15")
      (footprint "eagle-import:R1210")
      (libsource (lib "eagle-import") (part "resistor_R-US_R1210"))
    )
    (comp (ref "REGS")
      (value "MA04-1")
      (footprint "eagle-import:MA04-1")
      (libsource (lib "eagle-import") (part "MA04-1"))
    )
    (comp (ref "ROMS")
      (value "PINHD-1X3")
      (footprint "eagle-import:1X03")
      (libsource (lib "eagle-import") (part "PINHD-1X3"))
    )
    (comp (ref "RST")
      (value "DTS-6")
      (footprint "eagle-import:DTS-6")
      (libsource (lib "eagle-import") (part "DTS-6"))
    )
    (comp (ref "SPKR")
      (value "PINHD-1X2")
      (footprint "eagle-import:1X02")
      (libsource (lib "eagle-import") (part "PINHD-1X2"))
    )
    (comp (ref "T1")
      (value "BC847")
      (footprint "eagle-import:SOT23")
      (libsource (lib "eagle-import") (part "BC847"))
    )
    (comp (ref "T2")
      (value "4401")
      (footprint "eagle-import:SOT23-BEC")
      (libsource (lib "eagle-import") (part "-NPN-SOT23-BECMMBT4401LT1"))
    )
    (comp (ref "T3")
      (value "4401")
      (footprint "eagle-import:SOT23-BEC")
      (libsource (lib "eagle-import") (part "-NPN-SOT23-BECMMBT4401LT1"))
    )
    (comp (ref "T4")
      (value "BC847")
      (footprint "eagle-import:SOT23")
      (libsource (lib "eagle-import") (part "BC847"))
    )
    (comp (ref "T5")
      (value "4401")
      (footprint "eagle-import:SOT23-BEC")
      (libsource (lib "eagle-import") (part "-NPN-SOT23-BECMMBT4401LT1"))
    )
    (comp (ref "T6")
      (value "4401")
      (footprint "eagle-import:SOT23-BEC")
      (libsource (lib "eagle-import") (part "-NPN-SOT23-BECMMBT4401LT1"))
    )
    (comp (ref "T7")
      (value "4401")
      (footprint "eagle-import:SOT23-BEC")
      (libsource (lib "eagle-import") (part "-NPN-SOT23-BECMMBT4401LT1"))
    )
    (comp (ref "U$1")
      (value "MC74HC574A")
      (footprint "eagle-import:SO20W")
      (libsource (lib "eagle-import") (part "MC74HC574A"))
    )
    (comp (ref "U$2")
      (value "LM1889")
      (footprint "eagle-import:SOCKET-18")
      (libsource (lib "eagle-import") (part "LM1889"))
    )
    (comp (ref "U$3")
      (value "MS12ASW30_01")
      (footprint "eagle-import:MS12ASG30_01")
      (libsource (lib "eagle-import") (part "MS12ASW30_01"))
    )
    (comp (ref "ULA")
      (value "ZXULA")
      (footprint "eagle-import:DIL40")
      (libsource (lib "eagle-import") (part "ZXULA"))
    )
    (comp (ref "ULA_RAM")
      (value "CY62256LL-SNXI")
      (footprint "eagle-import:SOJ28_3")
      (libsource (lib "eagle-import") (part "CY62256LL-?SNXI"))
    )
    (comp (ref "VID")
      (value "PINHD-1X2")
      (footprint "eagle-import:1X02")
      (libsource (lib "eagle-import") (part "PINHD-1X2"))
    )
    (comp (ref "VPOW")
      (value "PINHD-1X2")
      (footprint "eagle-import:1X02")
      (libsource (lib "eagle-import") (part "PINHD-1X2"))
    )
    (comp (ref "Z80A")
      (value "Z80CPU")
      (footprint "eagle-import:DIL40")
      (libsource (lib "eagle-import") (part "Z80CPU"))
    )
    (comp (ref "C33")
      (value "10uF")
      (footprint "eagle-import:0805")
      (libsource (lib "eagle-import") (part "CAP_CERAMIC0805"))
    )
    (comp (ref "C34")
      (value "10uF")
      (footprint "eagle-import:0805")
      (libsource (lib "eagle-import") (part "CAP_CERAMIC0805"))
    )
    (comp (ref "JP3")
      (value "LOAD_0.1")
      (footprint "eagle-import:1X02_OVAL")
      (libsource (lib "eagle-import") (part "HEADER-1X2"))
    )
    (comp (ref "JP5")
      (value "BATT_IN_0.1")
      (footprint "eagle-import:1X02_OVAL")
      (libsource (lib "eagle-import") (part "HEADER-1X2"))
    )
    (comp (ref "LED1")
      (value "STAT1-ORANGE")
      (footprint "eagle-import:CHIPLED_0805")
      (libsource (lib "eagle-import") (part "LED0805"))
    )
    (comp (ref "LED2")
      (value "STAT2-GREEN")
      (footprint "eagle-import:CHIPLED_0805")
      (libsource (lib "eagle-import") (part "LED0805"))
    )
    (comp (ref "LED3")
      (value "Power-RED")
      (footprint "eagle-import:CHIPLED_0805")
      (libsource (lib "eagle-import") (part "LED0805"))
    )
    (comp (ref "R34")
      (value "150")
      (footprint "eagle-import:0805")
      (libsource (lib "eagle-import") (part "RESISTOR0805"))
    )
    (comp (ref "R63")
      (value "150")
      (footprint "eagle-import:0805")
      (libsource (lib "eagle-import") (part "RESISTOR0805"))
    )
    (comp (ref "R66")
      (value "150")
      (footprint "eagle-import:0805")
      (libsource (lib "eagle-import") (part "RESISTOR0805"))
    )
    (comp (ref "R67")
      (value "PROG")
      (footprint "eagle-import:0805-THM")
      (libsource (lib "eagle-import") (part "RESISTOR_DUAL"))
    )
    (comp (ref "R68")
      (value "10K/THERM")
      (footprint "eagle-import:0805-THM")
      (libsource (lib "eagle-import") (part "R-US_FLIPFLOP"))
    )
    (comp (ref "RT1")
      (value "1K")
      (footprint "eagle-import:R0805")
      (libsource (lib "eagle-import") (part "R-US_R0805"))
    )
    (comp (ref "RT2")
      (value "150K")
      (footprint "eagle-import:R0805")
      (libsource (lib "eagle-import") (part "R-US_R0805"))
    )
    (comp (ref "U1")
      (value "MCP73833-FCI/UN")
      (footprint "eagle-import:SOP50P490X110-10N")
      (libsource (lib "eagle-import") (part "MCP73833-FCI/UN"))
    )
  )
  (nets
    (net (code "1") (name "12V") (class "Default")
      (node (ref "C23") (pin "1") (pinfunction "1_1") (pintype "passive"))
      (node (ref "C24") (pin "1") (pinfunction "1_1") (pintype "passive"))
      (node (ref "R49") (pin "1") (pinfunction "1_1") (pintype "passive"))
      (node (ref "REGS") (pin "2") (pinfunction "2_2") (pintype "passive"))
      (node (ref "U$2") (pin "14") (pinfunction "RF_SUPPLY_14") (pintype "bidirectional"))
      (node (ref "U$2") (pin "15") (pinfunction "SOUND_TANK_15") (pintype "bidirectional"))
      (node (ref "U$2") (pin "16") (pinfunction "CHROMA_SUPPLY_16") (pintype "bidirectional"))
    )
    (net (code "2") (name "A0") (class "Default")
      (node (ref "157-1") (pin "6") (pinfunction "2B_6") (pintype "bidirectional"))
      (node (ref "32KRAM") (pin "21") (pinfunction "A0_21") (pintype "input"))
      (node (ref "32K_ROM") (pin "11") (pinfunction "A0_11") (pintype "input"))
      (node (ref "T7") (pin "B") (pinfunction "B_B") (pintype "passive"))
      (node (ref "Z80A") (pin "30") (pinfunction "A0_30") (pintype "output"))
    )
    (net (code "3") (name "A1") (class "Default")
      (node (ref "157-1") (pin "3") (pinfunction "1B_3") (pintype "bidirectional"))
      (node (ref "32KRAM") (pin "23") (pinfunction "A1_23") (pintype "input"))
      (node (ref "32K_ROM") (pin "10") (pinfunction "A1_10") (pintype "input"))
      (node (ref "Z80A") (pin "31") (pinfunction "A1_31") (pintype "output"))
    )
    (net (code "4") (name "A2") (class "Default")
      (node (ref "157") (pin "6") (pinfunction "2B_6") (pintype "bidirectional"))
      (node (ref "32KRAM") (pin "24") (pinfunction "A2_24") (pintype "input"))
      (node (ref "32K_ROM") (pin "9") (pinfunction "A2_9") (pintype "input"))
      (node (ref "Z80A") (pin "32") (pinfunction "A2_32") (pintype "output"))
    )
    (net (code "5") (name "A3") (class "Default")
      (node (ref "157") (pin "3") (pinfunction "1B_3") (pintype "bidirectional"))
      (node (ref "32KRAM") (pin "25") (pinfunction "A3_25") (pintype "input"))
      (node (ref "32K_ROM") (pin "8") (pinfunction "A3_8") (pintype "input"))
      (node (ref "Z80A") (pin "33") (pinfunction "A3_33") (pintype "output"))
    )
    (net (code "6") (name "A4") (class "Default")
      (node (ref "157") (pin "13") (pinfunction "4B_13") (pintype "bidirectional"))
      (node (ref "32KRAM") (pin "26") (pinfunction "A4_26") (pintype "input"))
      (node (ref "32K_ROM") (pin "7") (pinfunction "A4_7") (pintype "input"))
      (node (ref "Z80A") (pin "34") (pinfunction "A4_34") (pintype "output"))
    )
    (net (code "7") (name "A5") (class "Default")
      (node (ref "157") (pin "10") (pinfunction "3B_10") (pintype "bidirectional"))
      (node (ref "32KRAM") (pin "1") (pinfunction "A5_1") (pintype "input"))
      (node (ref "32K_ROM") (pin "6") (pinfunction "A5_6") (pintype "input"))
      (node (ref "Z80A") (pin "35") (pinfunction "A5_35") (pintype "output"))
    )
    (net (code "8") (name "A6") (class "Default")
      (node (ref "157-1") (pin "13") (pinfunction "4B_13") (pintype "bidirectional"))
      (node (ref "32KRAM") (pin "2") (pinfunction "A6_2") (pintype "input"))
      (node (ref "32K_ROM") (pin "5") (pinfunction "A6_5") (pintype "input"))
      (node (ref "Z80A") (pin "36") (pinfunction "A6_36") (pintype "output"))
    )
    (net (code "9") (name "A7") (class "Default")
      (node (ref "157-1") (pin "5") (pinfunction "2A_5") (pintype "bidirectional"))
      (node (ref "32KRAM") (pin "3") (pinfunction "A7_3") (pintype "input"))
      (node (ref "32K_ROM") (pin "4") (pinfunction "A7_4") (pintype "input"))
      (node (ref "Z80A") (pin "37") (pinfunction "A7_37") (pintype "output"))
    )
    (net (code "10") (name "A8") (class "Default")
      (node (ref "157-1") (pin "2") (pinfunction "1A_2") (pintype "bidirectional"))
      (node (ref "32KRAM") (pin "4") (pinfunction "A8_4") (pintype "input"))
      (node (ref "32K_ROM") (pin "29") (pinfunction "A8_29") (pintype "input"))
      (node (ref "D4") (pin "C") (pinfunction "C_C") (pintype "passive"))
      (node (ref "Z80A") (pin "38") (pinfunction "A8_38") (pintype "output"))
    )
    (net (code "11") (name "A9") (class "Default")
      (node (ref "157") (pin "5") (pinfunction "2A_5") (pintype "bidirectional"))
      (node (ref "32KRAM") (pin "5") (pinfunction "A9_5") (pintype "input"))
      (node (ref "32K_ROM") (pin "28") (pinfunction "A9_28") (pintype "input"))
      (node (ref "D3") (pin "C") (pinfunction "C_C") (pintype "passive"))
      (node (ref "Z80A") (pin "39") (pinfunction "A9_39") (pintype "output"))
    )
    (net (code "12") (name "A10") (class "Default")
      (node (ref "157") (pin "2") (pinfunction "1A_2") (pintype "bidirectional"))
      (node (ref "32KRAM") (pin "6") (pinfunction "A10_6") (pintype "input"))
      (node (ref "32K_ROM") (pin "24") (pinfunction "A10_24") (pintype "input"))
      (node (ref "D2") (pin "C") (pinfunction "C_C") (pintype "passive"))
      (node (ref "Z80A") (pin "40") (pinfunction "A10_40") (pintype "output"))
    )
    (net (code "13") (name "A11") (class "Default")
      (node (ref "157") (pin "14") (pinfunction "4A_14") (pintype "bidirectional"))
      (node (ref "32KRAM") (pin "7") (pinfunction "A11_7") (pintype "input"))
      (node (ref "32K_ROM") (pin "27") (pinfunction "A11_27") (pintype "input"))
      (node (ref "D1") (pin "C") (pinfunction "C_C") (pintype "passive"))
      (node (ref "Z80A") (pin "1") (pinfunction "A11_1") (pintype "output"))
    )
    (net (code "14") (name "A12") (class "Default")
      (node (ref "157") (pin "11") (pinfunction "3A_11") (pintype "bidirectional"))
      (node (ref "32KRAM") (pin "8") (pinfunction "A12_8") (pintype "input"))
      (node (ref "32K_ROM") (pin "3") (pinfunction "A12_3") (pintype "input"))
      (node (ref "D5") (pin "C") (pinfunction "C_C") (pintype "passive"))
      (node (ref "Z80A") (pin "2") (pinfunction "A12_2") (pintype "output"))
    )
    (net (code "15") (name "A13") (class "Default")
      (node (ref "157-1") (pin "14") (pinfunction "4A_14") (pintype "bidirectional"))
      (node (ref "32KRAM") (pin "9") (pinfunction "A13_9") (pintype "input"))
      (node (ref "32K_ROM") (pin "30") (pinfunction "A13_30") (pintype "input"))
      (node (ref "D6") (pin "C") (pinfunction "C_C") (pintype "passive"))
      (node (ref "Z80A") (pin "3") (pinfunction "A13_3") (pintype "output"))
    )
    (net (code "16") (name "A14") (class "Default")
      (node (ref "32KRAM") (pin "10") (pinfunction "A14_10") (pintype "input"))
      (node (ref "D7") (pin "C") (pinfunction "C_C") (pintype "passive"))
      (node (ref "ULA") (pin "36") (pinfunction "A14_36") (pintype "output"))
      (node (ref "Z80A") (pin "4") (pinfunction "A14_4") (pintype "output"))
    )
    (net (code "17") (name "A15") (class "Default")
      (node (ref "D8") (pin "C") (pinfunction "C_C") (pintype "passive"))
      (node (ref "IC3") (pin "1") (pinfunction "I_1") (pintype "input"))
      (node (ref "ULA") (pin "37") (pinfunction "A15_37") (pintype "output"))
      (node (ref "Z80A") (pin "5") (pinfunction "A15_5") (pintype "output"))
    )
    (net (code "18") (name "BATT") (class "Default")
      (node (ref "C34") (pin "1") (pinfunction "P$1_1") (pintype "passive"))
      (node (ref "JP3") (pin "2") (pinfunction "2_2") (pintype "passive"))
      (node (ref "JP5") (pin "2") (pinfunction "2_2") (pintype "passive"))
      (node (ref "U$3") (pin "2") (pinfunction "P_2") (pintype "passive"))
      (node (ref "U1") (pin "10") (pinfunction "VBAT_10") (pintype "output"))
      (node (ref "U1") (pin "9") (pinfunction "VBAT_2_9") (pintype "output"))
    )
    (net (code "19") (name "CHG_5V") (class "Default")
      (node (ref "C33") (pin "1") (pinfunction "P$1_1") (pintype "passive"))
      (node (ref "J1") (pin "V_BUS") (pinfunction "5V_V_BUS") (pintype "bidirectional"))
      (node (ref "LED1") (pin "A") (pinfunction "A_A") (pintype "passive"))
      (node (ref "LED2") (pin "A") (pinfunction "A_A") (pintype "passive"))
      (node (ref "LED3") (pin "A") (pinfunction "A_A") (pintype "passive"))
      (node (ref "U1") (pin "1") (pinfunction "VDD_2_1") (pintype "power_in"))
      (node (ref "U1") (pin "2") (pinfunction "VDD_2") (pintype "power_in"))
    )
    (net (code "20") (name "CPU_CLK") (class "Default")
      (node (ref "R31") (pin "2") (pinfunction "2_2") (pintype "passive"))
      (node (ref "T3") (pin "C") (pinfunction "C_C") (pintype "passive"))
      (node (ref "Z80A") (pin "6") (pinfunction "CLK_6") (pintype "input"))
    )
    (net (code "21") (name "CPU_INT") (class "Default")
      (node (ref "R33") (pin "1") (pinfunction "1_1") (pintype "passive"))
      (node (ref "Z80A") (pin "16") (pinfunction "INT_16") (pintype "input"))
    )
    (net (code "22") (name "D0") (class "Default")
      (node (ref "32KRAM") (pin "11") (pinfunction "DQ0_11") (pintype "bidirectional"))
      (node (ref "32K_ROM") (pin "13") (pinfunction "D0_13") (pintype "tri_state"))
      (node (ref "R11") (pin "1") (pinfunction "1_1") (pintype "passive"))
      (node (ref "R4") (pin "1") (pinfunction "1_1") (pintype "passive"))
      (node (ref "Z80A") (pin "14") (pinfunction "D0_14") (pintype "bidirectional"))
    )
    (net (code "23") (name "D1") (class "Default")
      (node (ref "32KRAM") (pin "12") (pinfunction "DQ1_12") (pintype "bidirectional"))
      (node (ref "32K_ROM") (pin "14") (pinfunction "D1_14") (pintype "tri_state"))
      (node (ref "R5") (pin "1") (pinfunction "1_1") (pintype "passive"))
      (node (ref "R9") (pin "1") (pinfunction "1_1") (pintype "passive"))
      (node (ref "Z80A") (pin "15") (pinfunction "D1_15") (pintype "bidirectional"))
    )
    (net (code "24") (name "D2") (class "Default")
      (node (ref "32KRAM") (pin "13") (pinfunction "DQ2_13") (pintype "bidirectional"))
      (node (ref "32K_ROM") (pin "15") (pinfunction "D2_15") (pintype "tri_state"))
      (node (ref "R10") (pin "1") (pinfunction "1_1") (pintype "passive"))
      (node (ref "R6") (pin "1") (pinfunction "1_1") (pintype "passive"))
      (node (ref "Z80A") (pin "12") (pinfunction "D2_12") (pintype "bidirectional"))
    )
    (net (code "25") (name "D3") (class "Default")
      (node (ref "32KRAM") (pin "15") (pinfunction "DQ3_15") (pintype "bidirectional"))
      (node (ref "32K_ROM") (pin "18") (pinfunction "D3_18") (pintype "tri_state"))
      (node (ref "R1") (pin "1") (pinfunction "1_1") (pintype "passive"))
      (node (ref "R12") (pin "1") (pinfunction "1_1") (pintype "passive"))
      (node (ref "Z80A") (pin "8") (pinfunction "D3_8") (pintype "bidirectional"))
    )
    (net (code "26") (name "D4") (class "Default")
      (node (ref "32KRAM") (pin "16") (pinfunction "DQ4_16") (pintype "bidirectional"))
      (node (ref "32K_ROM") (pin "19") (pinfunction "D4_19") (pintype "tri_state"))
      (node (ref "R13") (pin "1") (pinfunction "1_1") (pintype "passive"))
      (node (ref "R2") (pin "1") (pinfunction "1_1") (pintype "passive"))
      (node (ref "Z80A") (pin "7") (pinfunction "D4_7") (pintype "bidirectional"))
    )
    (net (code "27") (name "D5") (class "Default")
      (node (ref "32KRAM") (pin "17") (pinfunction "DQ5_17") (pintype "bidirectional"))
      (node (ref "32K_ROM") (pin "20") (pinfunction "D5_20") (pintype "tri_state"))
      (node (ref "R14") (pin "1") (pinfunction "1_1") (pintype "passive"))
      (node (ref "R3") (pin "1") (pinfunction "1_1") (pintype "passive"))
      (node (ref "Z80A") (pin "9") (pinfunction "D5_9") (pintype "bidirectional"))
    )
    (net (code "28") (name "D6") (class "Default")
      (node (ref "32KRAM") (pin "18") (pinfunction "DQ6_18") (pintype "bidirectional"))
      (node (ref "32K_ROM") (pin "21") (pinfunction "D6_21") (pintype "tri_state"))
      (node (ref "R15") (pin "1") (pinfunction "1_1") (pintype "passive"))
      (node (ref "R7") (pin "1") (pinfunction "1_1") (pintype "passive"))
      (node (ref "Z80A") (pin "10") (pinfunction "D6_10") (pintype "bidirectional"))
    )
    (net (code "29") (name "D7") (class "Default")
      (node (ref "32KRAM") (pin "19") (pinfunction "DQ7_19") (pintype "bidirectional"))
      (node (ref "32K_ROM") (pin "22") (pinfunction "D7_22") (pintype "tri_state"))
      (node (ref "R16") (pin "1") (pinfunction "1_1") (pintype "passive"))
      (node (ref "R8") (pin "1") (pinfunction "1_1") (pintype "passive"))
      (node (ref "Z80A") (pin "13") (pinfunction "D7_13") (pintype "bidirectional"))
    )
    (net (code "30") (name "EAR") (class "Default")
      (node (ref "JP1") (pin "RING") (pinfunction "RIGHT_RING") (pintype "bidirectional"))
      (node (ref "R36") (pin "2") (pinfunction "2_2") (pintype "passive"))
      (node (ref "R37") (pin "1") (pinfunction "1_1") (pintype "passive"))
    )
    (net (code "31") (name "FCLOCK") (class "Default")
      (node (ref "IC3") (pin "12") (pinfunction "O_12") (pintype "output"))
      (node (ref "U$1") (pin "11") (pinfunction "CLOCK_11") (pintype "bidirectional"))
    )
    (net (code "32") (name "GND") (class "Default")
      (node (ref "157") (pin "15") (pinfunction "G_15") (pintype "bidirectional"))
      (node (ref "157") (pin "8") (pinfunction "GND_8") (pintype "bidirectional"))
      (node (ref "157-1") (pin "15") (pinfunction "G_15") (pintype "bidirectional"))
      (node (ref "157-1") (pin "8") (pinfunction "GND_8") (pintype "bidirectional"))
      (node (ref "32KRAM") (pin "14") (pinfunction "GND_14") (pintype "power_in"))
      (node (ref "32K_ROM") (pin "16") (pinfunction "GND_16") (pintype "power_in"))
      (node (ref "BATT") (pin "1") (pinfunction "1_1") (pintype "passive"))
      (node (ref "BATT") (pin "2") (pinfunction "2_2") (pintype "passive"))
      (node (ref "C1") (pin "2") (pinfunction "2_2") (pintype "passive"))
      (node (ref "C11") (pin "2") (pinfunction "2_2") (pintype "passive"))
      (node (ref "C14") (pin "2") (pinfunction "2_2") (pintype "passive"))
      (node (ref "C19") (pin "2") (pinfunction "2_2") (pintype "passive"))
      (node (ref "C2") (pin "2") (pinfunction "2_2") (pintype "passive"))
      (node (ref "C20") (pin "2") (pinfunction "2_2") (pintype "passive"))
      (node (ref "C21") (pin "2") (pinfunction "2_2") (pintype "passive"))
      (node (ref "C22") (pin "2") (pinfunction "2_2") (pintype "passive"))
      (node (ref "C23") (pin "2") (pinfunction "2_2") (pintype "passive"))
      (node (ref "C24") (pin "2") (pinfunction "2_2") (pintype "passive"))
      (node (ref "C25") (pin "-") (pinfunction "-_-") (pintype "passive"))
      (node (ref "C26") (pin "2") (pinfunction "2_2") (pintype "passive"))
      (node (ref "C27") (pin "2") (pinfunction "2_2") (pintype "passive"))
      (node (ref "C28") (pin "-") (pinfunction "-_-") (pintype "passive"))
      (node (ref "C3") (pin "2") (pinfunction "2_2") (pintype "passive"))
      (node (ref "C30") (pin "-") (pinfunction "-_-") (pintype "passive"))
      (node (ref "C31") (pin "-") (pinfunction "-_-") (pintype "passive"))
      (node (ref "C32") (pin "2") (pinfunction "2_2") (pintype "passive"))
      (node (ref "C33") (pin "2") (pinfunction "P$2_2") (pintype "passive"))
      (node (ref "C34") (pin "2") (pinfunction "P$2_2") (pintype "passive"))
      (node (ref "C4") (pin "2") (pinfunction "2_2") (pintype "passive"))
      (node (ref "C6") (pin "2") (pinfunction "2_2") (pintype "passive"))
      (node (ref "C7") (pin "2") (pinfunction "2_2") (pintype "passive"))
      (node (ref "C8") (pin "2") (pinfunction "2_2") (pintype "passive"))
      (node (ref "D9") (pin "A") (pinfunction "A_A") (pintype "passive"))
      (node (ref "IC1") (pin "7") (pinfunction "GND_7") (pintype "power_in"))
      (node (ref "IC3") (pin "7") (pinfunction "GND_7") (pintype "power_in"))
      (node (ref "J1") (pin "GND") (pinfunction "GND_GND") (pintype "bidirectional"))
      (node (ref "J1") (pin "SH_0") (pinfunction "GND_SH_0") (pintype "bidirectional"))
      (node (ref "J1") (pin "SH_1") (pinfunction "GND_SH_1") (pintype "bidirectional"))
      (node (ref "J1") (pin "SH_2") (pinfunction "GND_SH_2") (pintype "bidirectional"))
      (node (ref "J1") (pin "SH_3") (pinfunction "GND_SH_3") (pintype "bidirectional"))
      (node (ref "JP1") (pin "SLEEVE") (pinfunction "SLEEVE_SLEEVE") (pintype "bidirectional"))
      (node (ref "JP3") (pin "1") (pinfunction "1_1") (pintype "passive"))
      (node (ref "JP5") (pin "1") (pinfunction "1_1") (pintype "passive"))
      (node (ref "R37") (pin "2") (pinfunction "2_2") (pintype "passive"))
      (node (ref "R41") (pin "2") (pinfunction "2_2") (pintype "passive"))
      (node (ref "R42") (pin "2") (pinfunction "2_2") (pintype "passive"))
      (node (ref "R43") (pin "1") (pinfunction "1_1") (pintype "passive"))
      (node (ref "R46") (pin "2") (pinfunction "2_2") (pintype "passive"))
      (node (ref "R50") (pin "1") (pinfunction "1_1") (pintype "passive"))
      (node (ref "R54") (pin "2") (pinfunction "2_2") (pintype "passive"))
      (node (ref "R55") (pin "2") (pinfunction "2_2") (pintype "passive"))
      (node (ref "R56") (pin "2") (pinfunction "2_2") (pintype "passive"))
      (node (ref "R67") (pin "1") (pinfunction "1_1") (pintype "passive"))
      (node (ref "R68") (pin "1") (pinfunction "1_1") (pintype "passive"))
      (node (ref "ROMS") (pin "1") (pinfunction "1_1") (pintype "passive"))
      (node (ref "RST") (pin "1") (pinfunction "1_1") (pintype "passive"))
      (node (ref "RT2") (pin "1") (pinfunction "1_1") (pintype "passive"))
      (node (ref "SPKR") (pin "2") (pinfunction "2_2") (pintype "passive"))
      (node (ref "T3") (pin "E") (pinfunction "E_E") (pintype "passive"))
      (node (ref "U$1") (pin "1") (pinfunction "OE_1") (pintype "bidirectional"))
      (node (ref "U$1") (pin "10") (pinfunction "GND_10") (pintype "bidirectional"))
      (node (ref "U$2") (pin "5") (pinfunction "GND_5") (pintype "bidirectional"))
      (node (ref "U1") (pin "5") (pinfunction "VSS_5") (pintype "passive"))
      (node (ref "ULA") (pin "40") (pinfunction "GND_40") (pintype "output"))
      (node (ref "ULA_RAM") (pin "10") (pinfunction "A14_10") (pintype "input"))
      (node (ref "ULA_RAM") (pin "14") (pinfunction "GND_14") (pintype "power_in"))
      (node (ref "ULA_RAM") (pin "22") (pinfunction "~{OE}_22") (pintype "input"))
      (node (ref "VID") (pin "2") (pinfunction "2_2") (pintype "passive"))
      (node (ref "VPOW") (pin "1") (pinfunction "1_1") (pintype "passive"))
      (node (ref "Z80A") (pin "29") (pinfunction "GND_29") (pintype "power_in"))
    )
    (net (code "33") (name "INTL") (class "Default")
      (node (ref "R33") (pin "2") (pinfunction "2_2") (pintype "passive"))
      (node (ref "ULA") (pin "12") (pinfunction "INTL_12") (pintype "input"))
    )
    (net (code "34") (name "IOREQL") (class "Default")
      (node (ref "R64") (pin "2") (pinfunction "2_2") (pintype "passive"))
      (node (ref "T7") (pin "E") (pinfunction "E_E") (pintype "passive"))
      (node (ref "ULA") (pin "33") (pinfunction "IOREQL_33") (pintype "output"))
    )
    (net (code "35") (name "IORQ") (class "Default")
      (node (ref "R64") (pin "1") (pinfunction "1_1") (pintype "passive"))
      (node (ref "Z80A") (pin "20") (pinfunction "IORQ_20") (pintype "output"))
    )
    (net (code "36") (name "KEY0") (class "Default")
      (node (ref "K0") (pin "1") (pinfunction "1_1") (pintype "passive"))
      (node (ref "K1") (pin "1") (pinfunction "1_1") (pintype "passive"))
      (node (ref "KA") (pin "1") (pinfunction "1_1") (pintype "passive"))
      (node (ref "KCAPS") (pin "1") (pinfunction "1_1") (pintype "passive"))
      (node (ref "KENT") (pin "1") (pinfunction "1_1") (pintype "passive"))
      (node (ref "KP") (pin "1") (pinfunction "1_1") (pintype "passive"))
      (node (ref "KQ") (pin "1") (pinfunction "1_1") (pintype "passive"))
      (node (ref "KSPACE") (pin "1") (pinfunction "1_1") (pintype "passive"))
      (node (ref "R21") (pin "1") (pinfunction "1_1") (pintype "passive"))
      (node (ref "ULA") (pin "19") (pinfunction "KB0_19") (pintype "output"))
    )
    (net (code "37") (name "KEY1") (class "Default")
      (node (ref "K2") (pin "1") (pinfunction "1_1") (pintype "passive"))
      (node (ref "K9") (pin "1") (pinfunction "1_1") (pintype "passive"))
      (node (ref "KL") (pin "1") (pinfunction "1_1") (pintype "passive"))
      (node (ref "KO") (pin "1") (pinfunction "1_1") (pintype "passive"))
      (node (ref "KS") (pin "1") (pinfunction "1_1") (pintype "passive"))
      (node (ref "KSYM") (pin "1") (pinfunction "1_1") (pintype "passive"))
      (node (ref "KW") (pin "1") (pinfunction "1_1") (pintype "passive"))
      (node (ref "KZ") (pin "1") (pinfunction "1_1") (pintype "passive"))
      (node (ref "R26") (pin "1") (pinfunction "1_1") (pintype "passive"))
      (node (ref "ULA") (pin "20") (pinfunction "KB1_20") (pintype "output"))
    )
    (net (code "38") (name "KEY2") (class "Default")
      (node (ref "K3") (pin "1") (pinfunction "1_1") (pintype "passive"))
      (node (ref "K8") (pin "1") (pinfunction "1_1") (pintype "passive"))
      (node (ref "KD") (pin "1") (pinfunction "1_1") (pintype "passive"))
      (node (ref "KE") (pin "1") (pinfunction "1_1") (pintype "passive"))
      (node (ref "KI") (pin "1") (pinfunction "1_1") (pintype "passive"))
      (node (ref "KK") (pin "1") (pinfunction "1_1") (pintype "passive"))
      (node (ref "KM") (pin "1") (pinfunction "1_1") (pintype "passive"))
      (node (ref "KX") (pin "1") (pinfunction "1_1") (pintype "passive"))
      (node (ref "R27") (pin "1") (pinfunction "1_1") (pintype "passive"))
      (node (ref "ULA") (pin "23") (pinfunction "KB2_23") (pintype "output"))
    )
    (net (code "39") (name "KEY3") (class "Default")
      (node (ref "K4") (pin "1") (pinfunction "1_1") (pintype "passive"))
      (node (ref "K7") (pin "1") (pinfunction "1_1") (pintype "passive"))
      (node (ref "KC") (pin "1") (pinfunction "1_1") (pintype "passive"))
      (node (ref "KF") (pin "1") (pinfunction "1_1") (pintype "passive"))
      (node (ref "KJ") (pin "1") (pinfunction "1_1") (pintype "passive"))
      (node (ref "KN") (pin "1") (pinfunction "1_1") (pintype "passive"))
      (node (ref "KR") (pin "1") (pinfunction "1_1") (pintype "passive"))
      (node (ref "KU") (pin "1") (pinfunction "1_1") (pintype "passive"))
      (node (ref "R28") (pin "1") (pinfunction "1_1") (pintype "passive"))
      (node (ref "ULA") (pin "24") (pinfunction "KB3_24") (pintype "output"))
    )
    (net (code "40") (name "KEY4") (class "Default")
      (node (ref "K5") (pin "1") (pinfunction "1_1") (pintype "passive"))
      (node (ref "K6") (pin "1") (pinfunction "1_1") (pintype "passive"))
      (node (ref "KB") (pin "1") (pinfunction "1_1") (pintype "passive"))
      (node (ref "KG") (pin "1") (pinfunction "1_1") (pintype "passive"))
      (node (ref "KH") (pin "1") (pinfunction "1_1") (pintype "passive"))
      (node (ref "KT") (pin "1") (pinfunction "1_1") (pintype "passive"))
      (node (ref "KV") (pin "1") (pinfunction "1_1") (pintype "passive"))
      (node (ref "KY") (pin "1") (pinfunction "1_1") (pintype "passive"))
      (node (ref "R29") (pin "1") (pinfunction "1_1") (pintype "passive"))
      (node (ref "ULA") (pin "26") (pinfunction "KB4_26") (pintype "output"))
    )
    (net (code "41") (name "MIC") (class "Default")
      (node (ref "C9") (pin "2") (pinfunction "2_2") (pintype "passive"))
      (node (ref "JP1") (pin "TIP") (pinfunction "LEFT_TIP") (pintype "bidirectional"))
    )
    (net (code "42") (name "MREQL") (class "Default")
      (node (ref "IC1") (pin "12") (pinfunction "I0_12") (pintype "input"))
      (node (ref "IC1") (pin "2") (pinfunction "I1_2") (pintype "input"))
      (node (ref "IC1") (pin "4") (pinfunction "I0_4") (pintype "input"))
      (node (ref "ULA") (pin "38") (pinfunction "MREQL_38") (pintype "output"))
      (node (ref "Z80A") (pin "19") (pinfunction "MREQ_19") (pintype "output"))
    )
    (net (code "43") (name "Net-(32K_ROM-A14)") (class "Default")
      (node (ref "32K_ROM") (pin "31") (pinfunction "A14_31") (pintype "input"))
      (node (ref "ROMS") (pin "2") (pinfunction "2_2") (pintype "passive"))
    )
    (net (code "44") (name "Net-(157-1-1Y)") (class "Default")
      (node (ref "157-1") (pin "4") (pinfunction "1Y_4") (pintype "bidirectional"))
      (node (ref "R19") (pin "1") (pinfunction "1_1") (pintype "passive"))
    )
    (net (code "45") (name "Net-(157-1-2Y)") (class "Default")
      (node (ref "157-1") (pin "7") (pinfunction "2Y_7") (pintype "bidirectional"))
      (node (ref "R20") (pin "1") (pinfunction "1_1") (pintype "passive"))
    )
    (net (code "46") (name "Net-(157-1-4Y)") (class "Default")
      (node (ref "157-1") (pin "12") (pinfunction "4Y_12") (pintype "bidirectional"))
      (node (ref "R22") (pin "2") (pinfunction "2_2") (pintype "passive"))
    )
    (net (code "47") (name "Net-(157-1-A{slash}B)") (class "Default")
      (node (ref "157") (pin "1") (pinfunction "A/B_1") (pintype "bidirectional"))
      (node (ref "157-1") (pin "1") (pinfunction "A/B_1") (pintype "bidirectional"))
      (node (ref "R25") (pin "1") (pinfunction "1_1") (pintype "passive"))
    )
    (net (code "48") (name "Net-(157-1Y)") (class "Default")
      (node (ref "157") (pin "4") (pinfunction "1Y_4") (pintype "bidirectional"))
      (node (ref "R17") (pin "1") (pinfunction "1_1") (pintype "passive"))
    )
    (net (code "49") (name "Net-(157-2Y)") (class "Default")
      (node (ref "157") (pin "7") (pinfunction "2Y_7") (pintype "bidirectional"))
      (node (ref "R18") (pin "1") (pinfunction "1_1") (pintype "passive"))
    )
    (net (code "50") (name "Net-(157-3Y)") (class "Default")
      (node (ref "157") (pin "9") (pinfunction "3Y_9") (pintype "bidirectional"))
      (node (ref "R23") (pin "2") (pinfunction "2_2") (pintype "passive"))
    )
    (net (code "51") (name "Net-(157-4Y)") (class "Default")
      (node (ref "157") (pin "12") (pinfunction "4Y_12") (pintype "bidirectional"))
      (node (ref "R24") (pin "2") (pinfunction "2_2") (pintype "passive"))
    )
    (net (code "52") (name "Net-(BATT-Pad3)") (class "Default")
      (node (ref "BATT") (pin "3") (pinfunction "3_3") (pintype "passive"))
      (node (ref "BATT") (pin "4") (pinfunction "4_4") (pintype "passive"))
    )
    (net (code "53") (name "Net-(C5-Pad2)") (class "Default")
      (node (ref "C5") (pin "2") (pinfunction "2_2") (pintype "passive"))
      (node (ref "R30") (pin "1") (pinfunction "1_1") (pintype "passive"))
      (node (ref "T3") (pin "B") (pinfunction "B_B") (pintype "passive"))
    )
    (net (code "54") (name "Net-(C9-Pad1)") (class "Default")
      (node (ref "C9") (pin "1") (pinfunction "1_1") (pintype "passive"))
      (node (ref "R35") (pin "2") (pinfunction "2_2") (pintype "passive"))
    )
    (net (code "55") (name "Net-(C10-Pad2)") (class "Default")
      (node (ref "C10") (pin "2") (pinfunction "2_2") (pintype "passive"))
      (node (ref "R36") (pin "1") (pinfunction "1_1") (pintype "passive"))
    )
    (net (code "56") (name "Net-(C17-Pad2)") (class "Default")
      (node (ref "C17") (pin "2") (pinfunction "2_2") (pintype "passive"))
      (node (ref "C18") (pin "1") (pinfunction "1_1") (pintype "passive"))
      (node (ref "R43") (pin "2") (pinfunction "2_2") (pintype "passive"))
    )
    (net (code "57") (name "Net-(C18-Pad2)") (class "Default")
      (node (ref "C18") (pin "2") (pinfunction "2_2") (pintype "passive"))
      (node (ref "Q2") (pin "2") (pinfunction "2_2") (pintype "passive"))
      (node (ref "R44") (pin "1") (pinfunction "1_1") (pintype "passive"))
    )
    (net (code "58") (name "Net-(C20-Pad1)") (class "Default")
      (node (ref "C20") (pin "1") (pinfunction "1_1") (pintype "passive"))
      (node (ref "Q2") (pin "1") (pinfunction "1_1") (pintype "passive"))
      (node (ref "R45") (pin "1") (pinfunction "1_1") (pintype "passive"))
    )
    (net (code "59") (name "Net-(C25-Pad+)") (class "Default")
      (node (ref "C25") (pin "+") (pinfunction "+_+") (pintype "passive"))
      (node (ref "C26") (pin "1") (pinfunction "1_1") (pintype "passive"))
      (node (ref "C27") (pin "1") (pinfunction "1_1") (pintype "passive"))
      (node (ref "R51") (pin "2") (pinfunction "2_2") (pintype "passive"))
      (node (ref "R52") (pin "1") (pinfunction "1_1") (pintype "passive"))
      (node (ref "R53") (pin "1") (pinfunction "1_1") (pintype "passive"))
      (node (ref "R58") (pin "1") (pinfunction "1_1") (pintype "passive"))
      (node (ref "T5") (pin "C") (pinfunction "C_C") (pintype "passive"))
    )
    (net (code "60") (name "Net-(C29-Pad-)") (class "Default")
      (node (ref "C29") (pin "-") (pinfunction "-_-") (pintype "passive"))
      (node (ref "R53") (pin "2") (pinfunction "2_2") (pintype "passive"))
      (node (ref "T5") (pin "B") (pinfunction "B_B") (pintype "passive"))
      (node (ref "T6") (pin "C") (pinfunction "C_C") (pintype "passive"))
    )
    (net (code "61") (name "Net-(C32-Pad1)") (class "Default")
      (node (ref "C32") (pin "1") (pinfunction "1_1") (pintype "passive"))
      (node (ref "Q1") (pin "1") (pinfunction "1_1") (pintype "passive"))
    )
    (net (code "62") (name "Net-(D1-PadA)") (class "Default")
      (node (ref "D1") (pin "A") (pinfunction "A_A") (pintype "passive"))
      (node (ref "K1") (pin "4") (pinfunction "4_4") (pintype "passive"))
      (node (ref "K2") (pin "4") (pinfunction "4_4") (pintype "passive"))
      (node (ref "K3") (pin "4") (pinfunction "4_4") (pintype "passive"))
      (node (ref "K4") (pin "4") (pinfunction "4_4") (pintype "passive"))
      (node (ref "K5") (pin "4") (pinfunction "4_4") (pintype "passive"))
    )
    (net (code "63") (name "Net-(D2-PadA)") (class "Default")
      (node (ref "D2") (pin "A") (pinfunction "A_A") (pintype "passive"))
      (node (ref "KE") (pin "4") (pinfunction "4_4") (pintype "passive"))
      (node (ref "KQ") (pin "4") (pinfunction "4_4") (pintype "passive"))
      (node (ref "KR") (pin "4") (pinfunction "4_4") (pintype "passive"))
      (node (ref "KT") (pin "4") (pinfunction "4_4") (pintype "passive"))
      (node (ref "KW") (pin "4") (pinfunction "4_4") (pintype "passive"))
    )
    (net (code "64") (name "Net-(D3-PadA)") (class "Default")
      (node (ref "D3") (pin "A") (pinfunction "A_A") (pintype "passive"))
      (node (ref "KA") (pin "4") (pinfunction "4_4") (pintype "passive"))
      (node (ref "KD") (pin "4") (pinfunction "4_4") (pintype "passive"))
      (node (ref "KF") (pin "4") (pinfunction "4_4") (pintype "passive"))
      (node (ref "KG") (pin "4") (pinfunction "4_4") (pintype "passive"))
      (node (ref "KS") (pin "4") (pinfunction "4_4") (pintype "passive"))
    )
    (net (code "65") (name "Net-(D4-PadA)") (class "Default")
      (node (ref "D4") (pin "A") (pinfunction "A_A") (pintype "passive"))
      (node (ref "KC") (pin "4") (pinfunction "4_4") (pintype "passive"))
      (node (ref "KCAPS") (pin "4") (pinfunction "4_4") (pintype "passive"))
      (node (ref "KV") (pin "4") (pinfunction "4_4") (pintype "passive"))
      (node (ref "KX") (pin "4") (pinfunction "4_4") (pintype "passive"))
      (node (ref "KZ") (pin "4") (pinfunction "4_4") (pintype "passive"))
    )
    (net (code "66") (name "Net-(D5-PadA)") (class "Default")
      (node (ref "D5") (pin "A") (pinfunction "A_A") (pintype "passive"))
      (node (ref "K0") (pin "4") (pinfunction "4_4") (pintype "passive"))
      (node (ref "K6") (pin "4") (pinfunction "4_4") (pintype "passive"))
      (node (ref "K7") (pin "4") (pinfunction "4_4") (pintype "passive"))
      (node (ref "K8") (pin "4") (pinfunction "4_4") (pintype "passive"))
      (node (ref "K9") (pin "4") (pinfunction "4_4") (pintype "passive"))
    )
    (net (code "67") (name "Net-(D6-PadA)") (class "Default")
      (node (ref "D6") (pin "A") (pinfunction "A_A") (pintype "passive"))
      (node (ref "KI") (pin "4") (pinfunction "4_4") (pintype "passive"))
      (node (ref "KO") (pin "4") (pinfunction "4_4") (pintype "passive"))
      (node (ref "KP") (pin "4") (pinfunction "4_4") (pintype "passive"))
      (node (ref "KU") (pin "4") (pinfunction "4_4") (pintype "passive"))
      (node (ref "KY") (pin "4") (pinfunction "4_4") (pintype "passive"))
    )
    (net (code "68") (name "Net-(D7-PadA)") (class "Default")
      (node (ref "D7") (pin "A") (pinfunction "A_A") (pintype "passive"))
      (node (ref "KENT") (pin "4") (pinfunction "4_4") (pintype "passive"))
      (node (ref "KH") (pin "4") (pinfunction "4_4") (pintype "passive"))
      (node (ref "KJ") (pin "4") (pinfunction "4_4") (pintype "passive"))
      (node (ref "KK") (pin "4") (pinfunction "4_4") (pintype "passive"))
      (node (ref "KL") (pin "4") (pinfunction "4_4") (pintype "passive"))
    )
    (net (code "69") (name "Net-(D8-PadA)") (class "Default")
      (node (ref "D8") (pin "A") (pinfunction "A_A") (pintype "passive"))
      (node (ref "KB") (pin "4") (pinfunction "4_4") (pintype "passive"))
      (node (ref "KM") (pin "4") (pinfunction "4_4") (pintype "passive"))
      (node (ref "KN") (pin "4") (pinfunction "4_4") (pintype "passive"))
      (node (ref "KSPACE") (pin "4") (pinfunction "4_4") (pintype "passive"))
      (node (ref "KSYM") (pin "4") (pinfunction "4_4") (pintype "passive"))
    )
    (net (code "70") (name "Net-(D10-PadC)") (class "Default")
      (node (ref "D10") (pin "C") (pinfunction "C_C") (pintype "passive"))
      (node (ref "T2") (pin "B") (pinfunction "B_B") (pintype "passive"))
    )
    (net (code "71") (name "Net-(LED1-PadC)") (class "Default")
      (node (ref "LED1") (pin "C") (pinfunction "C_C") (pintype "passive"))
      (node (ref "R34") (pin "2") (pinfunction "2_2") (pintype "passive"))
    )
    (net (code "72") (name "Net-(LED2-PadC)") (class "Default")
      (node (ref "LED2") (pin "C") (pinfunction "C_C") (pintype "passive"))
      (node (ref "R63") (pin "2") (pinfunction "2_2") (pintype "passive"))
    )
    (net (code "73") (name "Net-(LED3-PadC)") (class "Default")
      (node (ref "LED3") (pin "C") (pinfunction "C_C") (pintype "passive"))
      (node (ref "R66") (pin "1") (pinfunction "1_1") (pintype "passive"))
    )
    (net (code "74") (name "Net-(Q1-2)") (class "Default")
      (node (ref "Q1") (pin "3") (pinfunction "2_3") (pintype "passive"))
      (node (ref "ULA") (pin "39") (pinfunction "OSC_39") (pintype "output"))
    )
    (net (code "75") (name "Net-(R54-Pad1)") (class "Default")
      (node (ref "R54") (pin "1") (pinfunction "1_1") (pintype "passive"))
      (node (ref "T6") (pin "E") (pinfunction "E_E") (pintype "passive"))
    )
    (net (code "76") (name "Net-(R56-Pad1)") (class "Default")
      (node (ref "R56") (pin "1") (pinfunction "1_1") (pintype "passive"))
      (node (ref "R57") (pin "2") (pinfunction "2_2") (pintype "passive"))
      (node (ref "R58") (pin "2") (pinfunction "2_2") (pintype "passive"))
      (node (ref "T6") (pin "B") (pinfunction "B_B") (pintype "passive"))
    )
    (net (code "77") (name "Net-(R68-Pad2)") (class "Default")
      (node (ref "R68") (pin "2") (pinfunction "2_2") (pintype "passive"))
      (node (ref "RT1") (pin "2") (pinfunction "2_2") (pintype "passive"))
      (node (ref "RT2") (pin "2") (pinfunction "2_2") (pintype "passive"))
    )
    (net (code "78") (name "Net-(SPKR-Pad1)") (class "Default")
      (node (ref "SPKR") (pin "1") (pinfunction "1_1") (pintype "passive"))
      (node (ref "T2") (pin "E") (pinfunction "E_E") (pintype "passive"))
    )
    (net (code "79") (name "Net-(T1-B)") (class "Default")
      (node (ref "C13") (pin "2") (pinfunction "2_2") (pintype "passive"))
      (node (ref "R39") (pin "1") (pinfunction "1_1") (pintype "passive"))
      (node (ref "T1") (pin "1") (pinfunction "B_1") (pintype "passive"))
    )
    (net (code "80") (name "Net-(T1-C)") (class "Default")
      (node (ref "C16") (pin "1") (pinfunction "1_1") (pintype "passive"))
      (node (ref "R47") (pin "1") (pinfunction "1_1") (pintype "passive"))
      (node (ref "T1") (pin "3") (pinfunction "C_3") (pintype "passive"))
    )
    (net (code "81") (name "Net-(T4-B)") (class "Default")
      (node (ref "C12") (pin "2") (pinfunction "2_2") (pintype "passive"))
      (node (ref "R38") (pin "1") (pinfunction "1_1") (pintype "passive"))
      (node (ref "T4") (pin "1") (pinfunction "B_1") (pintype "passive"))
    )
    (net (code "82") (name "Net-(T4-C)") (class "Default")
      (node (ref "C15") (pin "1") (pinfunction "1_1") (pintype "passive"))
      (node (ref "R48") (pin "1") (pinfunction "1_1") (pintype "passive"))
      (node (ref "T4") (pin "3") (pinfunction "C_3") (pintype "passive"))
    )
    (net (code "83") (name "Net-(U$1-Q0)") (class "Default")
      (node (ref "U$1") (pin "19") (pinfunction "Q0_19") (pintype "bidirectional"))
      (node (ref "ULA_RAM") (pin "5") (pinfunction "A9_5") (pintype "input"))
    )
    (net (code "84") (name "Net-(U$1-Q1)") (class "Default")
      (node (ref "U$1") (pin "18") (pinfunction "Q1_18") (pintype "bidirectional"))
      (node (ref "ULA_RAM") (pin "3") (pinfunction "A7_3") (pintype "input"))
    )
    (net (code "85") (name "Net-(U$1-Q2)") (class "Default")
      (node (ref "U$1") (pin "17") (pinfunction "Q2_17") (pintype "bidirectional"))
      (node (ref "ULA_RAM") (pin "2") (pinfunction "A6_2") (pintype "input"))
    )
    (net (code "86") (name "Net-(U$1-Q3)") (class "Default")
      (node (ref "U$1") (pin "16") (pinfunction "Q3_16") (pintype "bidirectional"))
      (node (ref "ULA_RAM") (pin "26") (pinfunction "A4_26") (pintype "input"))
    )
    (net (code "87") (name "Net-(U$1-Q4)") (class "Default")
      (node (ref "U$1") (pin "15") (pinfunction "Q4_15") (pintype "bidirectional"))
      (node (ref "ULA_RAM") (pin "24") (pinfunction "A2_24") (pintype "input"))
    )
    (net (code "88") (name "Net-(U$1-Q5)") (class "Default")
      (node (ref "U$1") (pin "14") (pinfunction "Q5_14") (pintype "bidirectional"))
      (node (ref "ULA_RAM") (pin "23") (pinfunction "A1_23") (pintype "input"))
    )
    (net (code "89") (name "Net-(U$1-Q6)") (class "Default")
      (node (ref "U$1") (pin "13") (pinfunction "Q6_13") (pintype "bidirectional"))
      (node (ref "ULA_RAM") (pin "21") (pinfunction "A0_21") (pintype "input"))
    )
    (net (code "90") (name "Net-(U$2-CHROMA_BIAS)") (class "Default")
      (node (ref "C14") (pin "1") (pinfunction "1_1") (pintype "passive"))
      (node (ref "R40") (pin "2") (pinfunction "2_2") (pintype "passive"))
      (node (ref "U$2") (pin "3") (pinfunction "CHROMA_BIAS_3") (pintype "bidirectional"))
    )
    (net (code "91") (name "Net-(U$2-CHROMA_LAG)") (class "Default")
      (node (ref "C19") (pin "1") (pinfunction "1_1") (pintype "passive"))
      (node (ref "R44") (pin "2") (pinfunction "2_2") (pintype "passive"))
      (node (ref "U$2") (pin "18") (pinfunction "CHROMA_LAG_18") (pintype "bidirectional"))
    )
    (net (code "92") (name "Net-(U$2-CHROMA_LEAD)") (class "Default")
      (node (ref "C17") (pin "1") (pinfunction "1_1") (pintype "passive"))
      (node (ref "U$2") (pin "1") (pinfunction "CHROMA_LEAD_1") (pintype "bidirectional"))
    )
    (net (code "93") (name "Net-(U$2-CHROMA_OSC)") (class "Default")
      (node (ref "R45") (pin "2") (pinfunction "2_2") (pintype "passive"))
      (node (ref "R46") (pin "1") (pinfunction "1_1") (pintype "passive"))
      (node (ref "U$2") (pin "17") (pinfunction "CHROMA_OSC_17") (pintype "bidirectional"))
    )
    (net (code "94") (name "Net-(U$2-CHROMA_SUB)") (class "Default")
      (node (ref "C29") (pin "+") (pinfunction "+_+") (pintype "passive"))
      (node (ref "R51") (pin "1") (pinfunction "1_1") (pintype "passive"))
      (node (ref "U$2") (pin "13") (pinfunction "CHROMA_SUB_13") (pintype "bidirectional"))
    )
    (net (code "95") (name "Net-(U$2-U_INPUT)") (class "Default")
      (node (ref "C22") (pin "1") (pinfunction "1_1") (pintype "passive"))
      (node (ref "R47") (pin "2") (pinfunction "2_2") (pintype "passive"))
      (node (ref "U$2") (pin "4") (pinfunction "U_INPUT_4") (pintype "bidirectional"))
    )
    (net (code "96") (name "Net-(U$2-VIDEO_INPUT)") (class "Default")
      (node (ref "R49") (pin "2") (pinfunction "2_2") (pintype "passive"))
      (node (ref "U$2") (pin "12") (pinfunction "VIDEO_INPUT_12") (pintype "bidirectional"))
    )
    (net (code "97") (name "Net-(U$2-V_INPUT)") (class "Default")
      (node (ref "C21") (pin "1") (pinfunction "1_1") (pintype "passive"))
      (node (ref "R48") (pin "2") (pinfunction "2_2") (pintype "passive"))
      (node (ref "U$2") (pin "2") (pinfunction "V_INPUT_2") (pintype "bidirectional"))
    )
    (net (code "98") (name "Net-(U$3-S)") (class "Default")
      (node (ref "REGS") (pin "3") (pinfunction "3_3") (pintype "passive"))
      (node (ref "REGS") (pin "4") (pinfunction "4_4") (pintype "passive"))
      (node (ref "U$3") (pin "3") (pinfunction "S_3") (pintype "passive"))
      (node (ref "VPOW") (pin "2") (pinfunction "2_2") (pintype "passive"))
    )
    (net (code "99") (name "Net-(U1-*PG)") (class "Default")
      (node (ref "R66") (pin "2") (pinfunction "2_2") (pintype "passive"))
      (node (ref "U1") (pin "7") (pinfunction "*PG_7") (pintype "input"))
    )
    (net (code "100") (name "Net-(U1-PROG)") (class "Default")
      (node (ref "R67") (pin "2") (pinfunction "2_2") (pintype "passive"))
      (node (ref "U1") (pin "6") (pinfunction "PROG_6") (pintype "input"))
    )
    (net (code "101") (name "Net-(U1-STAT1)") (class "Default")
      (node (ref "R34") (pin "1") (pinfunction "1_1") (pintype "passive"))
      (node (ref "U1") (pin "3") (pinfunction "STAT1_3") (pintype "output"))
    )
    (net (code "102") (name "Net-(U1-STAT2)") (class "Default")
      (node (ref "R63") (pin "1") (pinfunction "1_1") (pintype "passive"))
      (node (ref "U1") (pin "4") (pinfunction "STAT2_4") (pintype "output"))
    )
    (net (code "103") (name "Net-(U1-THERM)") (class "Default")
      (node (ref "RT1") (pin "1") (pinfunction "1_1") (pintype "passive"))
      (node (ref "U1") (pin "8") (pinfunction "THERM_8") (pintype "input"))
    )
    (net (code "104") (name "Net-(ULA-CASL)") (class "Default")
      (node (ref "ULA") (pin "1") (pinfunction "CASL_1") (pintype "output"))
      (node (ref "ULA_RAM") (pin "20") (pinfunction "~{CE}_20") (pintype "input"))
    )
    (net (code "105") (name "Net-(ULA-CASS{slash}SPKR)") (class "Default")
      (node (ref "C10") (pin "1") (pinfunction "1_1") (pintype "passive"))
      (node (ref "C11") (pin "1") (pinfunction "1_1") (pintype "passive"))
      (node (ref "D10") (pin "A") (pinfunction "A_A") (pintype "passive"))
      (node (ref "D9") (pin "C") (pinfunction "C_C") (pintype "passive"))
      (node (ref "R35") (pin "1") (pinfunction "1_1") (pintype "passive"))
      (node (ref "ULA") (pin "28") (pinfunction "CASS/SPKR_28") (pintype "output"))
    )
    (net (code "106") (name "Net-(ULA-D0)") (class "Default")
      (node (ref "R4") (pin "2") (pinfunction "2_2") (pintype "passive"))
      (node (ref "ULA") (pin "18") (pinfunction "D0_18") (pintype "bidirectional"))
      (node (ref "ULA_RAM") (pin "11") (pinfunction "DQ0_11") (pintype "bidirectional"))
    )
    (net (code "107") (name "Net-(ULA-D1)") (class "Default")
      (node (ref "R5") (pin "2") (pinfunction "2_2") (pintype "passive"))
      (node (ref "ULA") (pin "21") (pinfunction "D1_21") (pintype "bidirectional"))
      (node (ref "ULA_RAM") (pin "12") (pinfunction "DQ1_12") (pintype "bidirectional"))
    )
    (net (code "108") (name "Net-(ULA-D2)") (class "Default")
      (node (ref "R6") (pin "2") (pinfunction "2_2") (pintype "passive"))
      (node (ref "ULA") (pin "22") (pinfunction "D2_22") (pintype "bidirectional"))
      (node (ref "ULA_RAM") (pin "13") (pinfunction "DQ2_13") (pintype "bidirectional"))
    )
    (net (code "109") (name "Net-(ULA-D3)") (class "Default")
      (node (ref "R1") (pin "2") (pinfunction "2_2") (pintype "passive"))
      (node (ref "ULA") (pin "25") (pinfunction "D3_25") (pintype "bidirectional"))
      (node (ref "ULA_RAM") (pin "15") (pinfunction "DQ3_15") (pintype "bidirectional"))
    )
    (net (code "110") (name "Net-(ULA-D4)") (class "Default")
      (node (ref "R2") (pin "2") (pinfunction "2_2") (pintype "passive"))
      (node (ref "ULA") (pin "27") (pinfunction "D4_27") (pintype "bidirectional"))
      (node (ref "ULA_RAM") (pin "16") (pinfunction "DQ4_16") (pintype "bidirectional"))
    )
    (net (code "111") (name "Net-(ULA-D5)") (class "Default")
      (node (ref "R3") (pin "2") (pinfunction "2_2") (pintype "passive"))
      (node (ref "ULA") (pin "29") (pinfunction "D5_29") (pintype "bidirectional"))
      (node (ref "ULA_RAM") (pin "17") (pinfunction "DQ5_17") (pintype "bidirectional"))
    )
    (net (code "112") (name "Net-(ULA-D6)") (class "Default")
      (node (ref "R7") (pin "2") (pinfunction "2_2") (pintype "passive"))
      (node (ref "ULA") (pin "30") (pinfunction "D6_30") (pintype "bidirectional"))
      (node (ref "ULA_RAM") (pin "18") (pinfunction "DQ6_18") (pintype "bidirectional"))
    )
    (net (code "113") (name "Net-(ULA-D7)") (class "Default")
      (node (ref "R8") (pin "2") (pinfunction "2_2") (pintype "passive"))
      (node (ref "ULA") (pin "31") (pinfunction "D7_31") (pintype "bidirectional"))
      (node (ref "ULA_RAM") (pin "19") (pinfunction "DQ7_19") (pintype "bidirectional"))
    )
    (net (code "114") (name "Net-(ULA-DRAMWEL)") (class "Default")
      (node (ref "ULA") (pin "4") (pinfunction "DRAMWEL_4") (pintype "output"))
      (node (ref "ULA_RAM") (pin "27") (pinfunction "~{WE}_27") (pintype "input"))
    )
    (net (code "115") (name "Net-(ULA-VCC{slash}VAN)") (class "Default")
      (node (ref "C7") (pin "1") (pinfunction "1_1") (pintype "passive"))
      (node (ref "R65") (pin "2") (pinfunction "2_2") (pintype "passive"))
      (node (ref "ULA") (pin "13") (pinfunction "VCC/VAN_13") (pintype "output"))
    )
    (net (code "116") (name "Net-(Z80A-BUSRQ)") (class "Default")
      (node (ref "R62") (pin "2") (pinfunction "2_2") (pintype "passive"))
      (node (ref "Z80A") (pin "25") (pinfunction "BUSRQ_25") (pintype "input"))
    )
    (net (code "117") (name "Net-(Z80A-NMI)") (class "Default")
      (node (ref "R61") (pin "2") (pinfunction "2_2") (pintype "passive"))
      (node (ref "Z80A") (pin "17") (pinfunction "NMI_17") (pintype "input"))
    )
    (net (code "118") (name "Net-(Z80A-RESET)") (class "Default")
      (node (ref "C28") (pin "+") (pinfunction "+_+") (pintype "passive"))
      (node (ref "R59") (pin "1") (pinfunction "1_1") (pintype "passive"))
      (node (ref "RST") (pin "3") (pinfunction "3_3") (pintype "passive"))
      (node (ref "Z80A") (pin "26") (pinfunction "RESET_26") (pintype "input"))
    )
    (net (code "119") (name "Net-(Z80A-WAIT)") (class "Default")
      (node (ref "R60") (pin "2") (pinfunction "2_2") (pintype "passive"))
      (node (ref "Z80A") (pin "24") (pinfunction "WAIT_24") (pintype "input"))
    )
    (net (code "120") (name "PHICPU") (class "Default")
      (node (ref "C5") (pin "1") (pinfunction "1_1") (pintype "passive"))
      (node (ref "R30") (pin "2") (pinfunction "2_2") (pintype "passive"))
      (node (ref "R32") (pin "2") (pinfunction "2_2") (pintype "passive"))
      (node (ref "ULA") (pin "32") (pinfunction "PHICPU_32") (pintype "output"))
    )
    (net (code "121") (name "RAM_CE") (class "Default")
      (node (ref "32KRAM") (pin "20") (pinfunction "~{CE}_20") (pintype "input"))
      (node (ref "IC3") (pin "2") (pinfunction "O_2") (pintype "output"))
    )
    (net (code "122") (name "RAM_OE") (class "Default")
      (node (ref "32KRAM") (pin "22") (pinfunction "~{OE}_22") (pintype "input"))
      (node (ref "IC1") (pin "3") (pinfunction "O_3") (pintype "output"))
    )
    (net (code "123") (name "RAM_WE") (class "Default")
      (node (ref "32KRAM") (pin "27") (pinfunction "~{WE}_27") (pintype "input"))
      (node (ref "IC1") (pin "6") (pinfunction "O_6") (pintype "output"))
    )
    (net (code "124") (name "RASL") (class "Default")
      (node (ref "IC3") (pin "13") (pinfunction "I_13") (pintype "input"))
      (node (ref "R25") (pin "2") (pinfunction "2_2") (pintype "passive"))
      (node (ref "ULA") (pin "35") (pinfunction "RASL_35") (pintype "output"))
    )
    (net (code "125") (name "READ") (class "Default")
      (node (ref "32K_ROM") (pin "25") (pinfunction "~{OE}_25") (pintype "input"))
      (node (ref "IC1") (pin "1") (pinfunction "I0_1") (pintype "input"))
      (node (ref "ULA") (pin "3") (pinfunction "RDL_3") (pintype "output"))
      (node (ref "Z80A") (pin "21") (pinfunction "RD_21") (pintype "output"))
    )
    (net (code "126") (name "ROM_CS") (class "Default")
      (node (ref "IC1") (pin "13") (pinfunction "I1_13") (pintype "input"))
      (node (ref "ULA") (pin "34") (pinfunction "ROMCSL_34") (pintype "output"))
    )
    (net (code "127") (name "ROM_SEL") (class "Default")
      (node (ref "32K_ROM") (pin "23") (pinfunction "~{CE}_23") (pintype "input"))
      (node (ref "IC1") (pin "11") (pinfunction "O_11") (pintype "output"))
    )
    (net (code "128") (name "URAMA0") (class "Default")
      (node (ref "R20") (pin "2") (pinfunction "2_2") (pintype "passive"))
      (node (ref "U$1") (pin "6") (pinfunction "D4_6") (pintype "bidirectional"))
      (node (ref "ULA") (pin "5") (pinfunction "DMA0_5") (pintype "output"))
      (node (ref "ULA_RAM") (pin "8") (pinfunction "A12_8") (pintype "input"))
    )
    (net (code "129") (name "URAMA1") (class "Default")
      (node (ref "R19") (pin "2") (pinfunction "2_2") (pintype "passive"))
      (node (ref "U$1") (pin "3") (pinfunction "D1_3") (pintype "bidirectional"))
      (node (ref "ULA") (pin "6") (pinfunction "DMA1_6") (pintype "output"))
      (node (ref "ULA_RAM") (pin "4") (pinfunction "A8_4") (pintype "input"))
    )
    (net (code "130") (name "URAMA2") (class "Default")
      (node (ref "R18") (pin "2") (pinfunction "2_2") (pintype "passive"))
      (node (ref "U$1") (pin "8") (pinfunction "D6_8") (pintype "bidirectional"))
      (node (ref "ULA") (pin "7") (pinfunction "DMA2_7") (pintype "output"))
      (node (ref "ULA_RAM") (pin "25") (pinfunction "A3_25") (pintype "input"))
    )
    (net (code "131") (name "URAMA3") (class "Default")
      (node (ref "R17") (pin "2") (pinfunction "2_2") (pintype "passive"))
      (node (ref "U$1") (pin "5") (pinfunction "D3_5") (pintype "bidirectional"))
      (node (ref "ULA") (pin "8") (pinfunction "DMA3_8") (pintype "input"))
      (node (ref "ULA_RAM") (pin "6") (pinfunction "A10_6") (pintype "input"))
    )
    (net (code "132") (name "URAMA4") (class "Default")
      (node (ref "R24") (pin "1") (pinfunction "1_1") (pintype "passive"))
      (node (ref "U$1") (pin "4") (pinfunction "D2_4") (pintype "bidirectional"))
      (node (ref "ULA") (pin "9") (pinfunction "DMA4_9") (pintype "input"))
      (node (ref "ULA_RAM") (pin "7") (pinfunction "A11_7") (pintype "input"))
    )
    (net (code "133") (name "URAMA5") (class "Default")
      (node (ref "R23") (pin "1") (pinfunction "1_1") (pintype "passive"))
      (node (ref "U$1") (pin "2") (pinfunction "D0_2") (pintype "bidirectional"))
      (node (ref "ULA") (pin "10") (pinfunction "DMA5_10") (pintype "input"))
      (node (ref "ULA_RAM") (pin "9") (pinfunction "A13_9") (pintype "input"))
    )
    (net (code "134") (name "URAMA6") (class "Default")
      (node (ref "R22") (pin "1") (pinfunction "1_1") (pintype "passive"))
      (node (ref "U$1") (pin "7") (pinfunction "D5_7") (pintype "bidirectional"))
      (node (ref "ULA") (pin "11") (pinfunction "DMA6_11") (pintype "input"))
      (node (ref "ULA_RAM") (pin "1") (pinfunction "A5_1") (pintype "input"))
    )
    (net (code "135") (name "VCC") (class "Default")
      (node (ref "157") (pin "16") (pinfunction "VCC_16") (pintype "bidirectional"))
      (node (ref "157-1") (pin "16") (pinfunction "VCC_16") (pintype "bidirectional"))
      (node (ref "32KRAM") (pin "28") (pinfunction "VCC_28") (pintype "power_in"))
      (node (ref "32K_ROM") (pin "2") (pinfunction "VPP_2") (pintype "input"))
      (node (ref "32K_ROM") (pin "32") (pinfunction "VCC_32") (pintype "power_in"))
      (node (ref "C1") (pin "1") (pinfunction "1_1") (pintype "passive"))
      (node (ref "C2") (pin "1") (pinfunction "1_1") (pintype "passive"))
      (node (ref "C3") (pin "1") (pinfunction "1_1") (pintype "passive"))
      (node (ref "C30") (pin "+") (pinfunction "+_+") (pintype "passive"))
      (node (ref "C31") (pin "+") (pinfunction "+_+") (pintype "passive"))
      (node (ref "C4") (pin "1") (pinfunction "1_1") (pintype "passive"))
      (node (ref "C6") (pin "1") (pinfunction "1_1") (pintype "passive"))
      (node (ref "C8") (pin "1") (pinfunction "1_1") (pintype "passive"))
      (node (ref "IC1") (pin "14") (pinfunction "VCC_14") (pintype "power_in"))
      (node (ref "IC3") (pin "14") (pinfunction "VCC_14") (pintype "power_in"))
      (node (ref "R10") (pin "2") (pinfunction "2_2") (pintype "passive"))
      (node (ref "R11") (pin "2") (pinfunction "2_2") (pintype "passive"))
      (node (ref "R12") (pin "2") (pinfunction "2_2") (pintype "passive"))
      (node (ref "R13") (pin "2") (pinfunction "2_2") (pintype "passive"))
      (node (ref "R14") (pin "2") (pinfunction "2_2") (pintype "passive"))
      (node (ref "R15") (pin "2") (pinfunction "2_2") (pintype "passive"))
      (node (ref "R16") (pin "2") (pinfunction "2_2") (pintype "passive"))
      (node (ref "R21") (pin "2") (pinfunction "2_2") (pintype "passive"))
      (node (ref "R26") (pin "2") (pinfunction "2_2") (pintype "passive"))
      (node (ref "R27") (pin "2") (pinfunction "2_2") (pintype "passive"))
      (node (ref "R28") (pin "2") (pinfunction "2_2") (pintype "passive"))
      (node (ref "R29") (pin "2") (pinfunction "2_2") (pintype "passive"))
      (node (ref "R31") (pin "1") (pinfunction "1_1") (pintype "passive"))
      (node (ref "R32") (pin "1") (pinfunction "1_1") (pintype "passive"))
      (node (ref "R38") (pin "2") (pinfunction "2_2") (pintype "passive"))
      (node (ref "R39") (pin "2") (pinfunction "2_2") (pintype "passive"))
      (node (ref "R40") (pin "1") (pinfunction "1_1") (pintype "passive"))
      (node (ref "R52") (pin "2") (pinfunction "2_2") (pintype "passive"))
      (node (ref "R59") (pin "2") (pinfunction "2_2") (pintype "passive"))
      (node (ref "R60") (pin "1") (pinfunction "1_1") (pintype "passive"))
      (node (ref "R61") (pin "1") (pinfunction "1_1") (pintype "passive"))
      (node (ref "R62") (pin "1") (pinfunction "1_1") (pintype "passive"))
      (node (ref "R65") (pin "1") (pinfunction "1_1") (pintype "passive"))
      (node (ref "R9") (pin "2") (pinfunction "2_2") (pintype "passive"))
      (node (ref "REGS") (pin "1") (pinfunction "1_1") (pintype "passive"))
      (node (ref "ROMS") (pin "3") (pinfunction "3_3") (pintype "passive"))
      (node (ref "T1") (pin "2") (pinfunction "E_2") (pintype "passive"))
      (node (ref "T2") (pin "C") (pinfunction "C_C") (pintype "passive"))
      (node (ref "T4") (pin "2") (pinfunction "E_2") (pintype "passive"))
      (node (ref "T7") (pin "C") (pinfunction "C_C") (pintype "passive"))
      (node (ref "U$1") (pin "20") (pinfunction "VCC_20") (pintype "bidirectional"))
      (node (ref "ULA") (pin "14") (pinfunction "VCC_14") (pintype "output"))
      (node (ref "ULA_RAM") (pin "28") (pinfunction "VCC_28") (pintype "power_in"))
      (node (ref "Z80A") (pin "11") (pinfunction "VCC_11") (pintype "power_in"))
    )
    (net (code "136") (name "VIDEO") (class "Default")
      (node (ref "R55") (pin "1") (pinfunction "1_1") (pintype "passive"))
      (node (ref "T5") (pin "E") (pinfunction "E_E") (pintype "passive"))
      (node (ref "VID") (pin "1") (pinfunction "1_1") (pintype "passive"))
    )
    (net (code "137") (name "VID_U") (class "Default")
      (node (ref "C16") (pin "2") (pinfunction "2_2") (pintype "passive"))
      (node (ref "R42") (pin "1") (pinfunction "1_1") (pintype "passive"))
      (node (ref "ULA") (pin "15") (pinfunction "U_15") (pintype "output"))
    )
    (net (code "138") (name "VID_V") (class "Default")
      (node (ref "C15") (pin "2") (pinfunction "2_2") (pintype "passive"))
      (node (ref "R41") (pin "1") (pinfunction "1_1") (pintype "passive"))
      (node (ref "ULA") (pin "16") (pinfunction "V_16") (pintype "output"))
    )
    (net (code "139") (name "VID_YL") (class "Default")
      (node (ref "C12") (pin "1") (pinfunction "1_1") (pintype "passive"))
      (node (ref "C13") (pin "1") (pinfunction "1_1") (pintype "passive"))
      (node (ref "R50") (pin "2") (pinfunction "2_2") (pintype "passive"))
      (node (ref "R57") (pin "1") (pinfunction "1_1") (pintype "passive"))
      (node (ref "ULA") (pin "17") (pinfunction "YL_17") (pintype "output"))
    )
    (net (code "140") (name "WRITE") (class "Default")
      (node (ref "IC1") (pin "5") (pinfunction "I1_5") (pintype "input"))
      (node (ref "ULA") (pin "2") (pinfunction "WRL_2") (pintype "output"))
      (node (ref "Z80A") (pin "22") (pinfunction "WR_22") (pintype "output"))
    )
    (net (code "141") (name "unconnected-(157-1-3A-Pad11)") (class "Default")
      (node (ref "157-1") (pin "11") (pinfunction "3A_11") (pintype "bidirectional"))
    )
    (net (code "142") (name "unconnected-(157-1-3B-Pad10)") (class "Default")
      (node (ref "157-1") (pin "10") (pinfunction "3B_10") (pintype "bidirectional"))
    )
    (net (code "143") (name "unconnected-(157-1-3Y-Pad9)") (class "Default")
      (node (ref "157-1") (pin "9") (pinfunction "3Y_9") (pintype "bidirectional"))
    )
    (net (code "144") (name "unconnected-(IC1C-I0-Pad9)") (class "Default")
      (node (ref "IC1") (pin "9") (pinfunction "I0_9") (pintype "input"))
    )
    (net (code "145") (name "unconnected-(IC1C-I1-Pad10)") (class "Default")
      (node (ref "IC1") (pin "10") (pinfunction "I1_10") (pintype "input"))
    )
    (net (code "146") (name "unconnected-(IC1C-O-Pad8)") (class "Default")
      (node (ref "IC1") (pin "8") (pinfunction "O_8") (pintype "output"))
    )
    (net (code "147") (name "unconnected-(IC3B-I-Pad3)") (class "Default")
      (node (ref "IC3") (pin "3") (pinfunction "I_3") (pintype "input"))
    )
    (net (code "148") (name "unconnected-(IC3B-O-Pad4)") (class "Default")
      (node (ref "IC3") (pin "4") (pinfunction "O_4") (pintype "output"))
    )
    (net (code "149") (name "unconnected-(IC3C-I-Pad5)") (class "Default")
      (node (ref "IC3") (pin "5") (pinfunction "I_5") (pintype "input"))
    )
    (net (code "150") (name "unconnected-(IC3C-O-Pad6)") (class "Default")
      (node (ref "IC3") (pin "6") (pinfunction "O_6") (pintype "output"))
    )
    (net (code "151") (name "unconnected-(IC3D-I-Pad9)") (class "Default")
      (node (ref "IC3") (pin "9") (pinfunction "I_9") (pintype "input"))
    )
    (net (code "152") (name "unconnected-(IC3D-O-Pad8)") (class "Default")
      (node (ref "IC3") (pin "8") (pinfunction "O_8") (pintype "output"))
    )
    (net (code "153") (name "unconnected-(IC3E-I-Pad11)") (class "Default")
      (node (ref "IC3") (pin "11") (pinfunction "I_11") (pintype "input"))
    )
    (net (code "154") (name "unconnected-(IC3E-O-Pad10)") (class "Default")
      (node (ref "IC3") (pin "10") (pinfunction "O_10") (pintype "output"))
    )
    (net (code "155") (name "unconnected-(J1-ID-PadN{slash}C)") (class "Default")
      (node (ref "J1") (pin "N/C") (pinfunction "ID_N/C") (pintype "bidirectional"))
    )
    (net (code "156") (name "unconnected-(J1-PadD+)") (class "Default")
      (node (ref "J1") (pin "D+") (pinfunction "D+_D+") (pintype "bidirectional"))
    )
    (net (code "157") (name "unconnected-(J1-PadD-)") (class "Default")
      (node (ref "J1") (pin "D-") (pinfunction "D-_D-") (pintype "bidirectional"))
    )
    (net (code "158") (name "unconnected-(K0-Pad2)") (class "Default")
      (node (ref "K0") (pin "2") (pinfunction "2_2") (pintype "passive"))
    )
    (net (code "159") (name "unconnected-(K0-Pad3)") (class "Default")
      (node (ref "K0") (pin "3") (pinfunction "3_3") (pintype "passive"))
    )
    (net (code "160") (name "unconnected-(K1-Pad2)") (class "Default")
      (node (ref "K1") (pin "2") (pinfunction "2_2") (pintype "passive"))
    )
    (net (code "161") (name "unconnected-(K1-Pad3)") (class "Default")
      (node (ref "K1") (pin "3") (pinfunction "3_3") (pintype "passive"))
    )
    (net (code "162") (name "unconnected-(K2-Pad2)") (class "Default")
      (node (ref "K2") (pin "2") (pinfunction "2_2") (pintype "passive"))
    )
    (net (code "163") (name "unconnected-(K2-Pad3)") (class "Default")
      (node (ref "K2") (pin "3") (pinfunction "3_3") (pintype "passive"))
    )
    (net (code "164") (name "unconnected-(K3-Pad2)") (class "Default")
      (node (ref "K3") (pin "2") (pinfunction "2_2") (pintype "passive"))
    )
    (net (code "165") (name "unconnected-(K3-Pad3)") (class "Default")
      (node (ref "K3") (pin "3") (pinfunction "3_3") (pintype "passive"))
    )
    (net (code "166") (name "unconnected-(K4-Pad2)") (class "Default")
      (node (ref "K4") (pin "2") (pinfunction "2_2") (pintype "passive"))
    )
    (net (code "167") (name "unconnected-(K4-Pad3)") (class "Default")
      (node (ref "K4") (pin "3") (pinfunction "3_3") (pintype "passive"))
    )
    (net (code "168") (name "unconnected-(K5-Pad2)") (class "Default")
      (node (ref "K5") (pin "2") (pinfunction "2_2") (pintype "passive"))
    )
    (net (code "169") (name "unconnected-(K5-Pad3)") (class "Default")
      (node (ref "K5") (pin "3") (pinfunction "3_3") (pintype "passive"))
    )
    (net (code "170") (name "unconnected-(K6-Pad2)") (class "Default")
      (node (ref "K6") (pin "2") (pinfunction "2_2") (pintype "passive"))
    )
    (net (code "171") (name "unconnected-(K6-Pad3)") (class "Default")
      (node (ref "K6") (pin "3") (pinfunction "3_3") (pintype "passive"))
    )
    (net (code "172") (name "unconnected-(K7-Pad2)") (class "Default")
      (node (ref "K7") (pin "2") (pinfunction "2_2") (pintype "passive"))
    )
    (net (code "173") (name "unconnected-(K7-Pad3)") (class "Default")
      (node (ref "K7") (pin "3") (pinfunction "3_3") (pintype "passive"))
    )
    (net (code "174") (name "unconnected-(K8-Pad2)") (class "Default")
      (node (ref "K8") (pin "2") (pinfunction "2_2") (pintype "passive"))
    )
    (net (code "175") (name "unconnected-(K8-Pad3)") (class "Default")
      (node (ref "K8") (pin "3") (pinfunction "3_3") (pintype "passive"))
    )
    (net (code "176") (name "unconnected-(K9-Pad2)") (class "Default")
      (node (ref "K9") (pin "2") (pinfunction "2_2") (pintype "passive"))
    )
    (net (code "177") (name "unconnected-(K9-Pad3)") (class "Default")
      (node (ref "K9") (pin "3") (pinfunction "3_3") (pintype "passive"))
    )
    (net (code "178") (name "unconnected-(KA-Pad2)") (class "Default")
      (node (ref "KA") (pin "2") (pinfunction "2_2") (pintype "passive"))
    )
    (net (code "179") (name "unconnected-(KA-Pad3)") (class "Default")
      (node (ref "KA") (pin "3") (pinfunction "3_3") (pintype "passive"))
    )
    (net (code "180") (name "unconnected-(KB-Pad2)") (class "Default")
      (node (ref "KB") (pin "2") (pinfunction "2_2") (pintype "passive"))
    )
    (net (code "181") (name "unconnected-(KB-Pad3)") (class "Default")
      (node (ref "KB") (pin "3") (pinfunction "3_3") (pintype "passive"))
    )
    (net (code "182") (name "unconnected-(KC-Pad2)") (class "Default")
      (node (ref "KC") (pin "2") (pinfunction "2_2") (pintype "passive"))
    )
    (net (code "183") (name "unconnected-(KC-Pad3)") (class "Default")
      (node (ref "KC") (pin "3") (pinfunction "3_3") (pintype "passive"))
    )
    (net (code "184") (name "unconnected-(KCAPS-Pad2)") (class "Default")
      (node (ref "KCAPS") (pin "2") (pinfunction "2_2") (pintype "passive"))
    )
    (net (code "185") (name "unconnected-(KCAPS-Pad3)") (class "Default")
      (node (ref "KCAPS") (pin "3") (pinfunction "3_3") (pintype "passive"))
    )
    (net (code "186") (name "unconnected-(KD-Pad2)") (class "Default")
      (node (ref "KD") (pin "2") (pinfunction "2_2") (pintype "passive"))
    )
    (net (code "187") (name "unconnected-(KD-Pad3)") (class "Default")
      (node (ref "KD") (pin "3") (pinfunction "3_3") (pintype "passive"))
    )
    (net (code "188") (name "unconnected-(KE-Pad2)") (class "Default")
      (node (ref "KE") (pin "2") (pinfunction "2_2") (pintype "passive"))
    )
    (net (code "189") (name "unconnected-(KE-Pad3)") (class "Default")
      (node (ref "KE") (pin "3") (pinfunction "3_3") (pintype "passive"))
    )
    (net (code "190") (name "unconnected-(KENT-Pad2)") (class "Default")
      (node (ref "KENT") (pin "2") (pinfunction "2_2") (pintype "passive"))
    )
    (net (code "191") (name "unconnected-(KENT-Pad3)") (class "Default")
      (node (ref "KENT") (pin "3") (pinfunction "3_3") (pintype "passive"))
    )
    (net (code "192") (name "unconnected-(KF-Pad2)") (class "Default")
      (node (ref "KF") (pin "2") (pinfunction "2_2") (pintype "passive"))
    )
    (net (code "193") (name "unconnected-(KF-Pad3)") (class "Default")
      (node (ref "KF") (pin "3") (pinfunction "3_3") (pintype "passive"))
    )
    (net (code "194") (name "unconnected-(KG-Pad2)") (class "Default")
      (node (ref "KG") (pin "2") (pinfunction "2_2") (pintype "passive"))
    )
    (net (code "195") (name "unconnected-(KG-Pad3)") (class "Default")
      (node (ref "KG") (pin "3") (pinfunction "3_3") (pintype "passive"))
    )
    (net (code "196") (name "unconnected-(KH-Pad2)") (class "Default")
      (node (ref "KH") (pin "2") (pinfunction "2_2") (pintype "passive"))
    )
    (net (code "197") (name "unconnected-(KH-Pad3)") (class "Default")
      (node (ref "KH") (pin "3") (pinfunction "3_3") (pintype "passive"))
    )
    (net (code "198") (name "unconnected-(KI-Pad2)") (class "Default")
      (node (ref "KI") (pin "2") (pinfunction "2_2") (pintype "passive"))
    )
    (net (code "199") (name "unconnected-(KI-Pad3)") (class "Default")
      (node (ref "KI") (pin "3") (pinfunction "3_3") (pintype "passive"))
    )
    (net (code "200") (name "unconnected-(KJ-Pad2)") (class "Default")
      (node (ref "KJ") (pin "2") (pinfunction "2_2") (pintype "passive"))
    )
    (net (code "201") (name "unconnected-(KJ-Pad3)") (class "Default")
      (node (ref "KJ") (pin "3") (pinfunction "3_3") (pintype "passive"))
    )
    (net (code "202") (name "unconnected-(KK-Pad2)") (class "Default")
      (node (ref "KK") (pin "2") (pinfunction "2_2") (pintype "passive"))
    )
    (net (code "203") (name "unconnected-(KK-Pad3)") (class "Default")
      (node (ref "KK") (pin "3") (pinfunction "3_3") (pintype "passive"))
    )
    (net (code "204") (name "unconnected-(KL-Pad2)") (class "Default")
      (node (ref "KL") (pin "2") (pinfunction "2_2") (pintype "passive"))
    )
    (net (code "205") (name "unconnected-(KL-Pad3)") (class "Default")
      (node (ref "KL") (pin "3") (pinfunction "3_3") (pintype "passive"))
    )
    (net (code "206") (name "unconnected-(KM-Pad2)") (class "Default")
      (node (ref "KM") (pin "2") (pinfunction "2_2") (pintype "passive"))
    )
    (net (code "207") (name "unconnected-(KM-Pad3)") (class "Default")
      (node (ref "KM") (pin "3") (pinfunction "3_3") (pintype "passive"))
    )
    (net (code "208") (name "unconnected-(KN-Pad2)") (class "Default")
      (node (ref "KN") (pin "2") (pinfunction "2_2") (pintype "passive"))
    )
    (net (code "209") (name "unconnected-(KN-Pad3)") (class "Default")
      (node (ref "KN") (pin "3") (pinfunction "3_3") (pintype "passive"))
    )
    (net (code "210") (name "unconnected-(KO-Pad2)") (class "Default")
      (node (ref "KO") (pin "2") (pinfunction "2_2") (pintype "passive"))
    )
    (net (code "211") (name "unconnected-(KO-Pad3)") (class "Default")
      (node (ref "KO") (pin "3") (pinfunction "3_3") (pintype "passive"))
    )
    (net (code "212") (name "unconnected-(KP-Pad2)") (class "Default")
      (node (ref "KP") (pin "2") (pinfunction "2_2") (pintype "passive"))
    )
    (net (code "213") (name "unconnected-(KP-Pad3)") (class "Default")
      (node (ref "KP") (pin "3") (pinfunction "3_3") (pintype "passive"))
    )
    (net (code "214") (name "unconnected-(KQ-Pad2)") (class "Default")
      (node (ref "KQ") (pin "2") (pinfunction "2_2") (pintype "passive"))
    )
    (net (code "215") (name "unconnected-(KQ-Pad3)") (class "Default")
      (node (ref "KQ") (pin "3") (pinfunction "3_3") (pintype "passive"))
    )
    (net (code "216") (name "unconnected-(KR-Pad2)") (class "Default")
      (node (ref "KR") (pin "2") (pinfunction "2_2") (pintype "passive"))
    )
    (net (code "217") (name "unconnected-(KR-Pad3)") (class "Default")
      (node (ref "KR") (pin "3") (pinfunction "3_3") (pintype "passive"))
    )
    (net (code "218") (name "unconnected-(KS-Pad2)") (class "Default")
      (node (ref "KS") (pin "2") (pinfunction "2_2") (pintype "passive"))
    )
    (net (code "219") (name "unconnected-(KS-Pad3)") (class "Default")
      (node (ref "KS") (pin "3") (pinfunction "3_3") (pintype "passive"))
    )
    (net (code "220") (name "unconnected-(KSPACE-Pad2)") (class "Default")
      (node (ref "KSPACE") (pin "2") (pinfunction "2_2") (pintype "passive"))
    )
    (net (code "221") (name "unconnected-(KSPACE-Pad3)") (class "Default")
      (node (ref "KSPACE") (pin "3") (pinfunction "3_3") (pintype "passive"))
    )
    (net (code "222") (name "unconnected-(KSYM-Pad2)") (class "Default")
      (node (ref "KSYM") (pin "2") (pinfunction "2_2") (pintype "passive"))
    )
    (net (code "223") (name "unconnected-(KSYM-Pad3)") (class "Default")
      (node (ref "KSYM") (pin "3") (pinfunction "3_3") (pintype "passive"))
    )
    (net (code "224") (name "unconnected-(KT-Pad2)") (class "Default")
      (node (ref "KT") (pin "2") (pinfunction "2_2") (pintype "passive"))
    )
    (net (code "225") (name "unconnected-(KT-Pad3)") (class "Default")
      (node (ref "KT") (pin "3") (pinfunction "3_3") (pintype "passive"))
    )
    (net (code "226") (name "unconnected-(KU-Pad2)") (class "Default")
      (node (ref "KU") (pin "2") (pinfunction "2_2") (pintype "passive"))
    )
    (net (code "227") (name "unconnected-(KU-Pad3)") (class "Default")
      (node (ref "KU") (pin "3") (pinfunction "3_3") (pintype "passive"))
    )
    (net (code "228") (name "unconnected-(KV-Pad2)") (class "Default")
      (node (ref "KV") (pin "2") (pinfunction "2_2") (pintype "passive"))
    )
    (net (code "229") (name "unconnected-(KV-Pad3)") (class "Default")
      (node (ref "KV") (pin "3") (pinfunction "3_3") (pintype "passive"))
    )
    (net (code "230") (name "unconnected-(KW-Pad2)") (class "Default")
      (node (ref "KW") (pin "2") (pinfunction "2_2") (pintype "passive"))
    )
    (net (code "231") (name "unconnected-(KW-Pad3)") (class "Default")
      (node (ref "KW") (pin "3") (pinfunction "3_3") (pintype "passive"))
    )
    (net (code "232") (name "unconnected-(KX-Pad2)") (class "Default")
      (node (ref "KX") (pin "2") (pinfunction "2_2") (pintype "passive"))
    )
    (net (code "233") (name "unconnected-(KX-Pad3)") (class "Default")
      (node (ref "KX") (pin "3") (pinfunction "3_3") (pintype "passive"))
    )
    (net (code "234") (name "unconnected-(KY-Pad2)") (class "Default")
      (node (ref "KY") (pin "2") (pinfunction "2_2") (pintype "passive"))
    )
    (net (code "235") (name "unconnected-(KY-Pad3)") (class "Default")
      (node (ref "KY") (pin "3") (pinfunction "3_3") (pintype "passive"))
    )
    (net (code "236") (name "unconnected-(KZ-Pad2)") (class "Default")
      (node (ref "KZ") (pin "2") (pinfunction "2_2") (pintype "passive"))
    )
    (net (code "237") (name "unconnected-(KZ-Pad3)") (class "Default")
      (node (ref "KZ") (pin "3") (pinfunction "3_3") (pintype "passive"))
    )
    (net (code "238") (name "unconnected-(RST-Pad2)") (class "Default")
      (node (ref "RST") (pin "2") (pinfunction "2_2") (pintype "passive"))
    )
    (net (code "239") (name "unconnected-(RST-Pad4)") (class "Default")
      (node (ref "RST") (pin "4") (pinfunction "4_4") (pintype "passive"))
    )
    (net (code "240") (name "unconnected-(U$1-D7-Pad9)") (class "Default")
      (node (ref "U$1") (pin "9") (pinfunction "D7_9") (pintype "bidirectional"))
    )
    (net (code "241") (name "unconnected-(U$1-Q7-Pad12)") (class "Default")
      (node (ref "U$1") (pin "12") (pinfunction "Q7_12") (pintype "bidirectional"))
    )
    (net (code "242") (name "unconnected-(U$2-CHA_OUTPUT-Pad11)") (class "Default")
      (node (ref "U$2") (pin "11") (pinfunction "CHA_OUTPUT_11") (pintype "bidirectional"))
    )
    (net (code "243") (name "unconnected-(U$2-CHA_TANK0-Pad8)") (class "Default")
      (node (ref "U$2") (pin "8") (pinfunction "CHA_TANK0_8") (pintype "bidirectional"))
    )
    (net (code "244") (name "unconnected-(U$2-CHA_TANK1-Pad9)") (class "Default")
      (node (ref "U$2") (pin "9") (pinfunction "CHA_TANK1_9") (pintype "bidirectional"))
    )
    (net (code "245") (name "unconnected-(U$2-CHB_OUTPUT-Pad10)") (class "Default")
      (node (ref "U$2") (pin "10") (pinfunction "CHB_OUTPUT_10") (pintype "bidirectional"))
    )
    (net (code "246") (name "unconnected-(U$2-CHB_TANK0-Pad6)") (class "Default")
      (node (ref "U$2") (pin "6") (pinfunction "CHB_TANK0_6") (pintype "bidirectional"))
    )
    (net (code "247") (name "unconnected-(U$2-CHB_TANK1-Pad7)") (class "Default")
      (node (ref "U$2") (pin "7") (pinfunction "CHB_TANK1_7") (pintype "bidirectional"))
    )
    (net (code "248") (name "unconnected-(U$3-O-Pad1)") (class "Default")
      (node (ref "U$3") (pin "1") (pinfunction "O_1") (pintype "passive"))
    )
    (net (code "249") (name "unconnected-(Z80A-BUSAK-Pad23)") (class "Default")
      (node (ref "Z80A") (pin "23") (pinfunction "BUSAK_23") (pintype "output"))
    )
    (net (code "250") (name "unconnected-(Z80A-HALT-Pad18)") (class "Default")
      (node (ref "Z80A") (pin "18") (pinfunction "HALT_18") (pintype "output"))
    )
    (net (code "251") (name "unconnected-(Z80A-M1-Pad27)") (class "Default")
      (node (ref "Z80A") (pin "27") (pinfunction "M1_27") (pintype "output"))
    )
    (net (code "252") (name "unconnected-(Z80A-RFSH-Pad28)") (class "Default")
      (node (ref "Z80A") (pin "28") (pinfunction "RFSH_28") (pintype "output"))
    )
  )
)
